# SBC_65C02_IRQ_BigBoard_v9-1-3.net
KiCad netlist of a schematic drawn in EAGLE
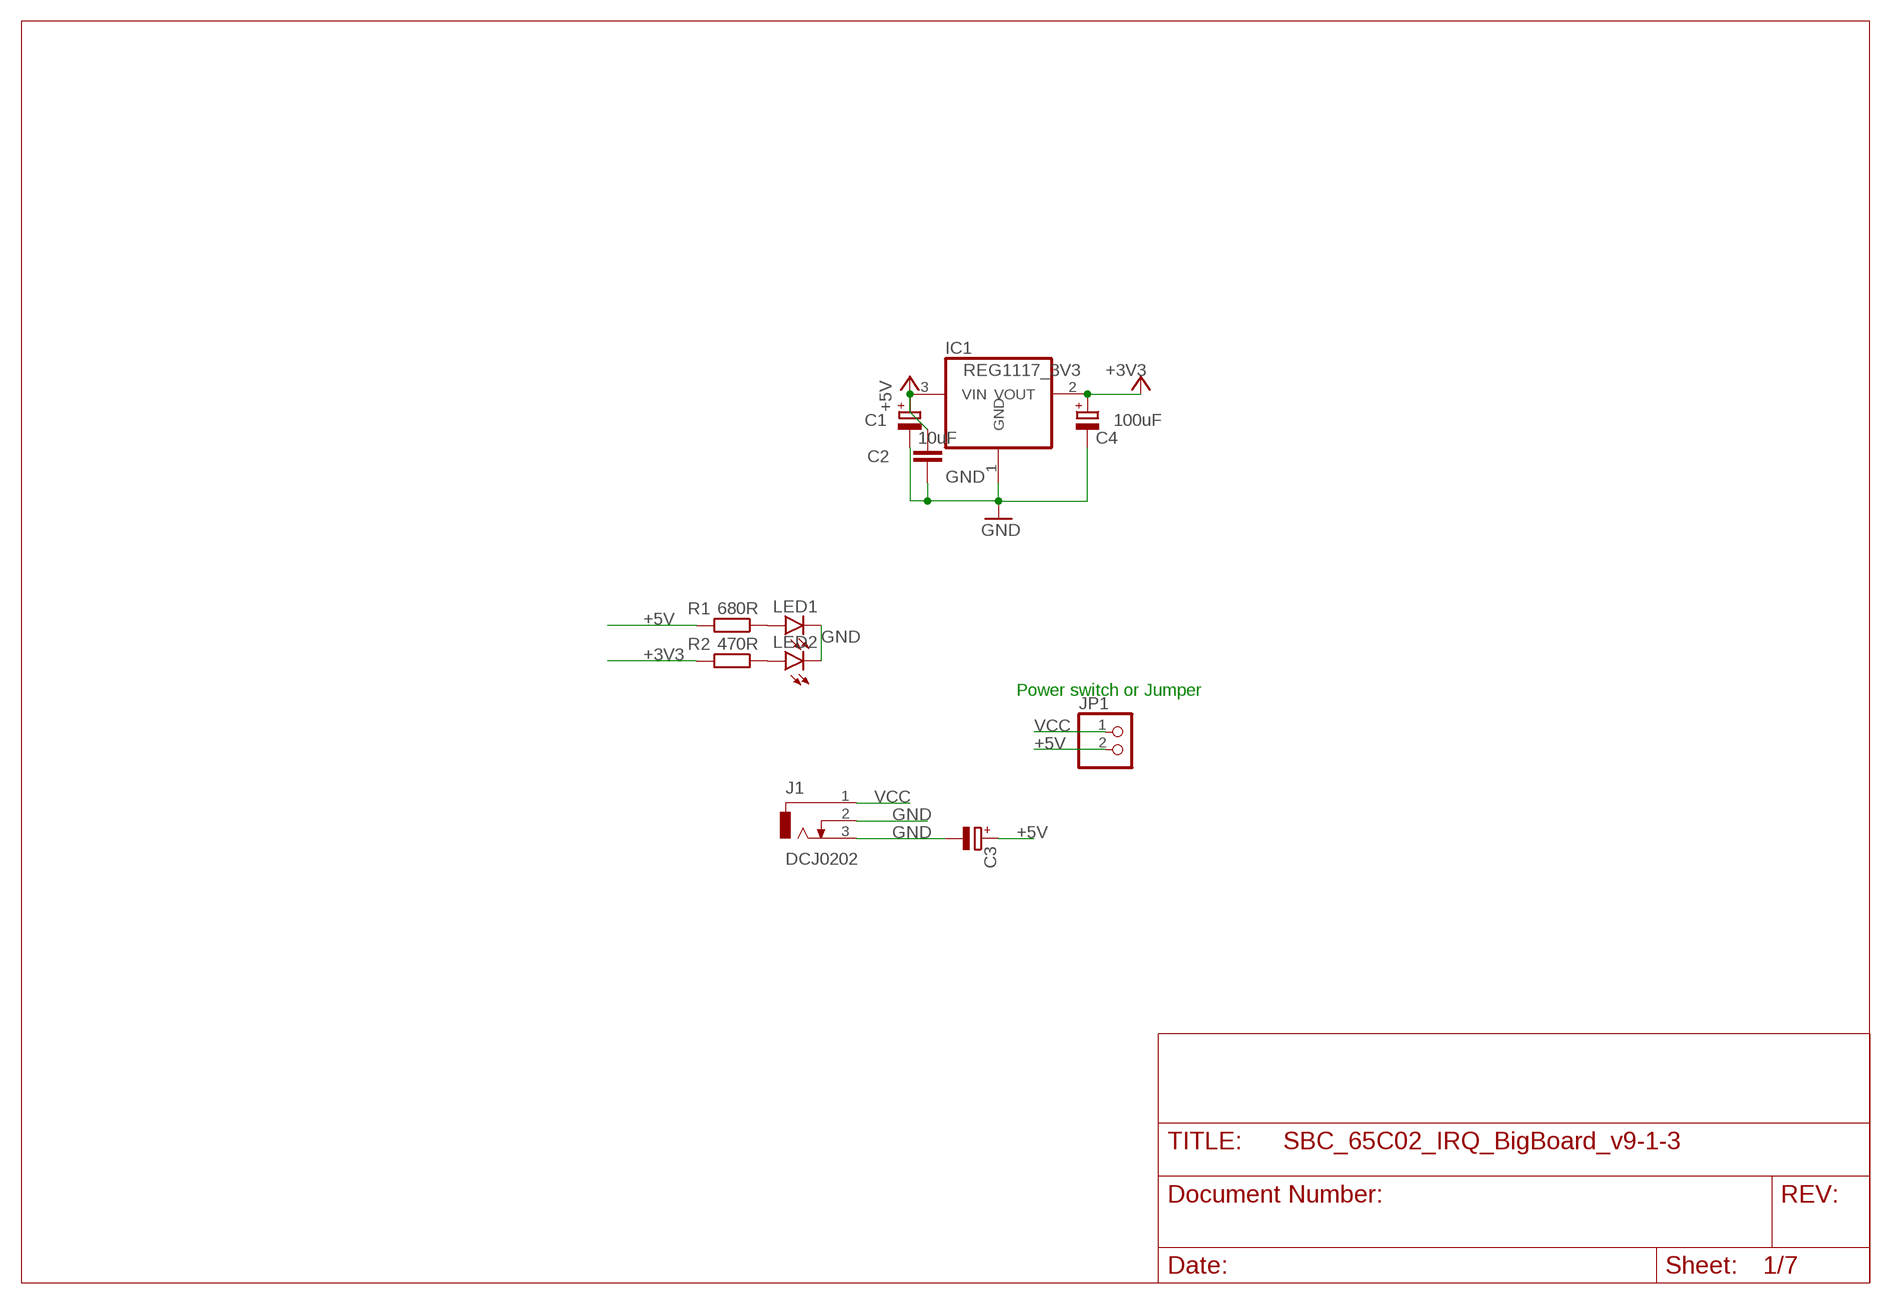
[diagram p0: schematic, sheet 1]
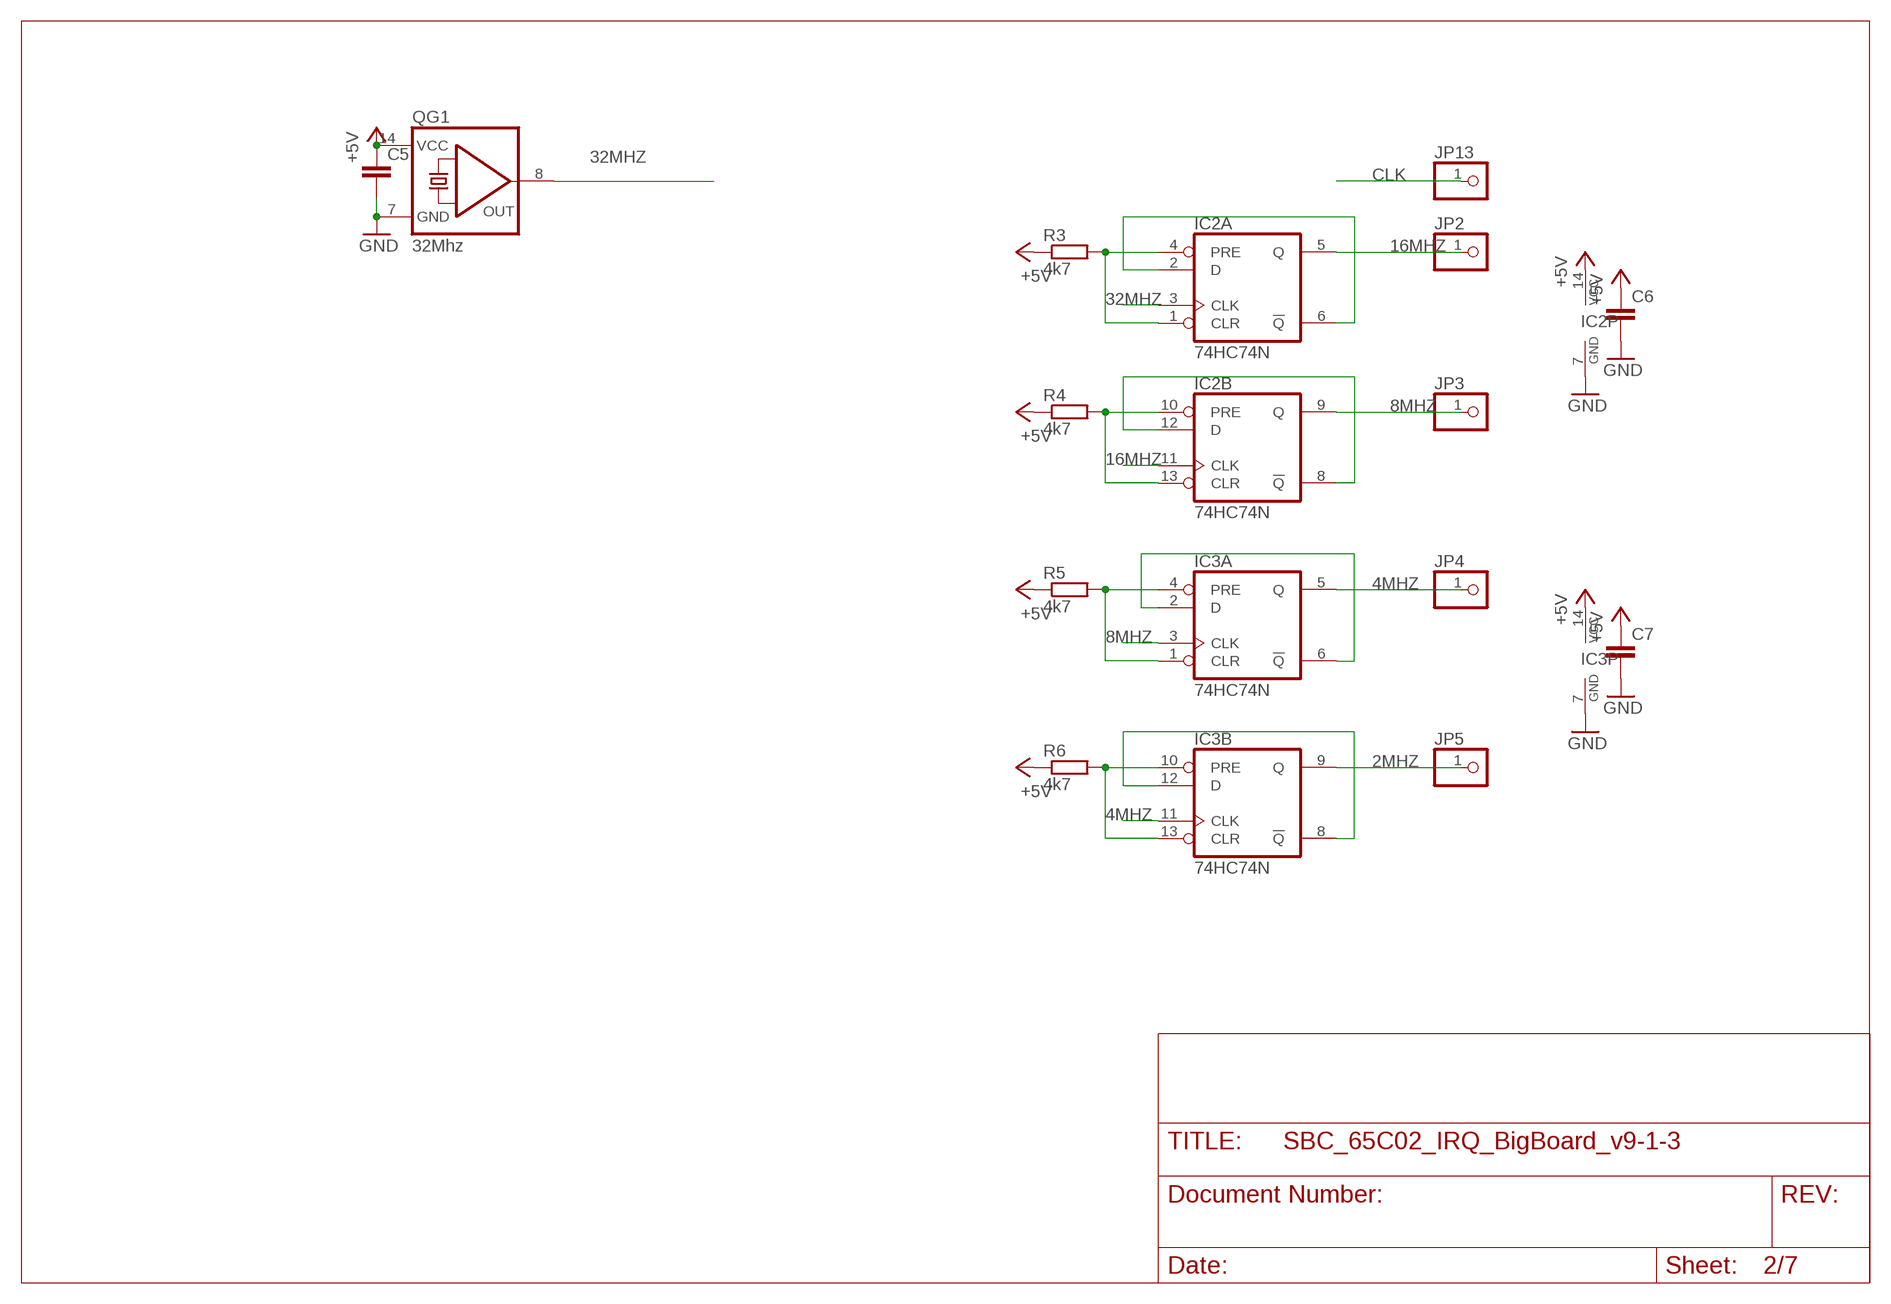
[diagram p1: schematic, sheet 2]
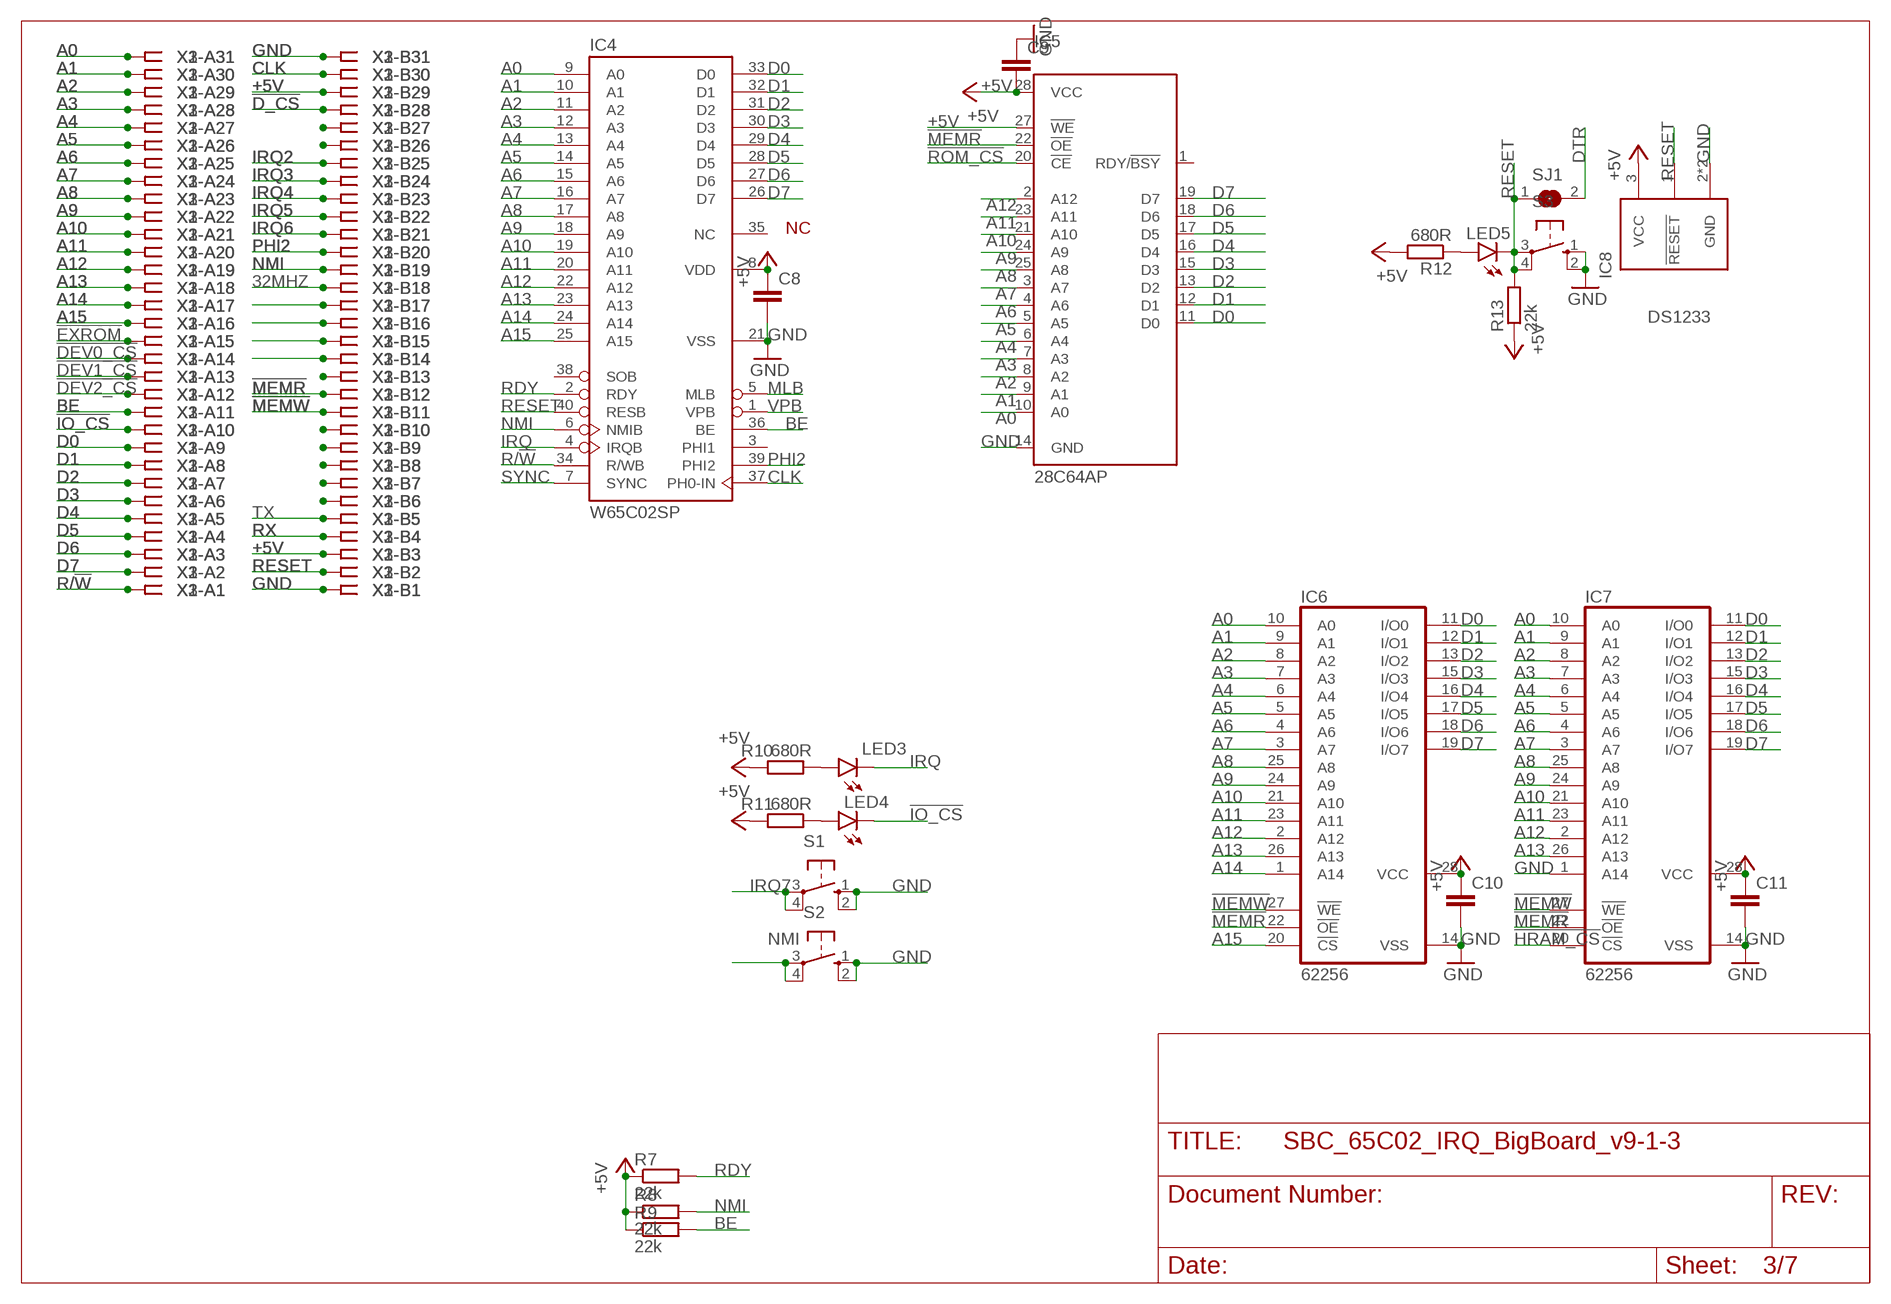
[diagram p2: schematic, sheet 3]
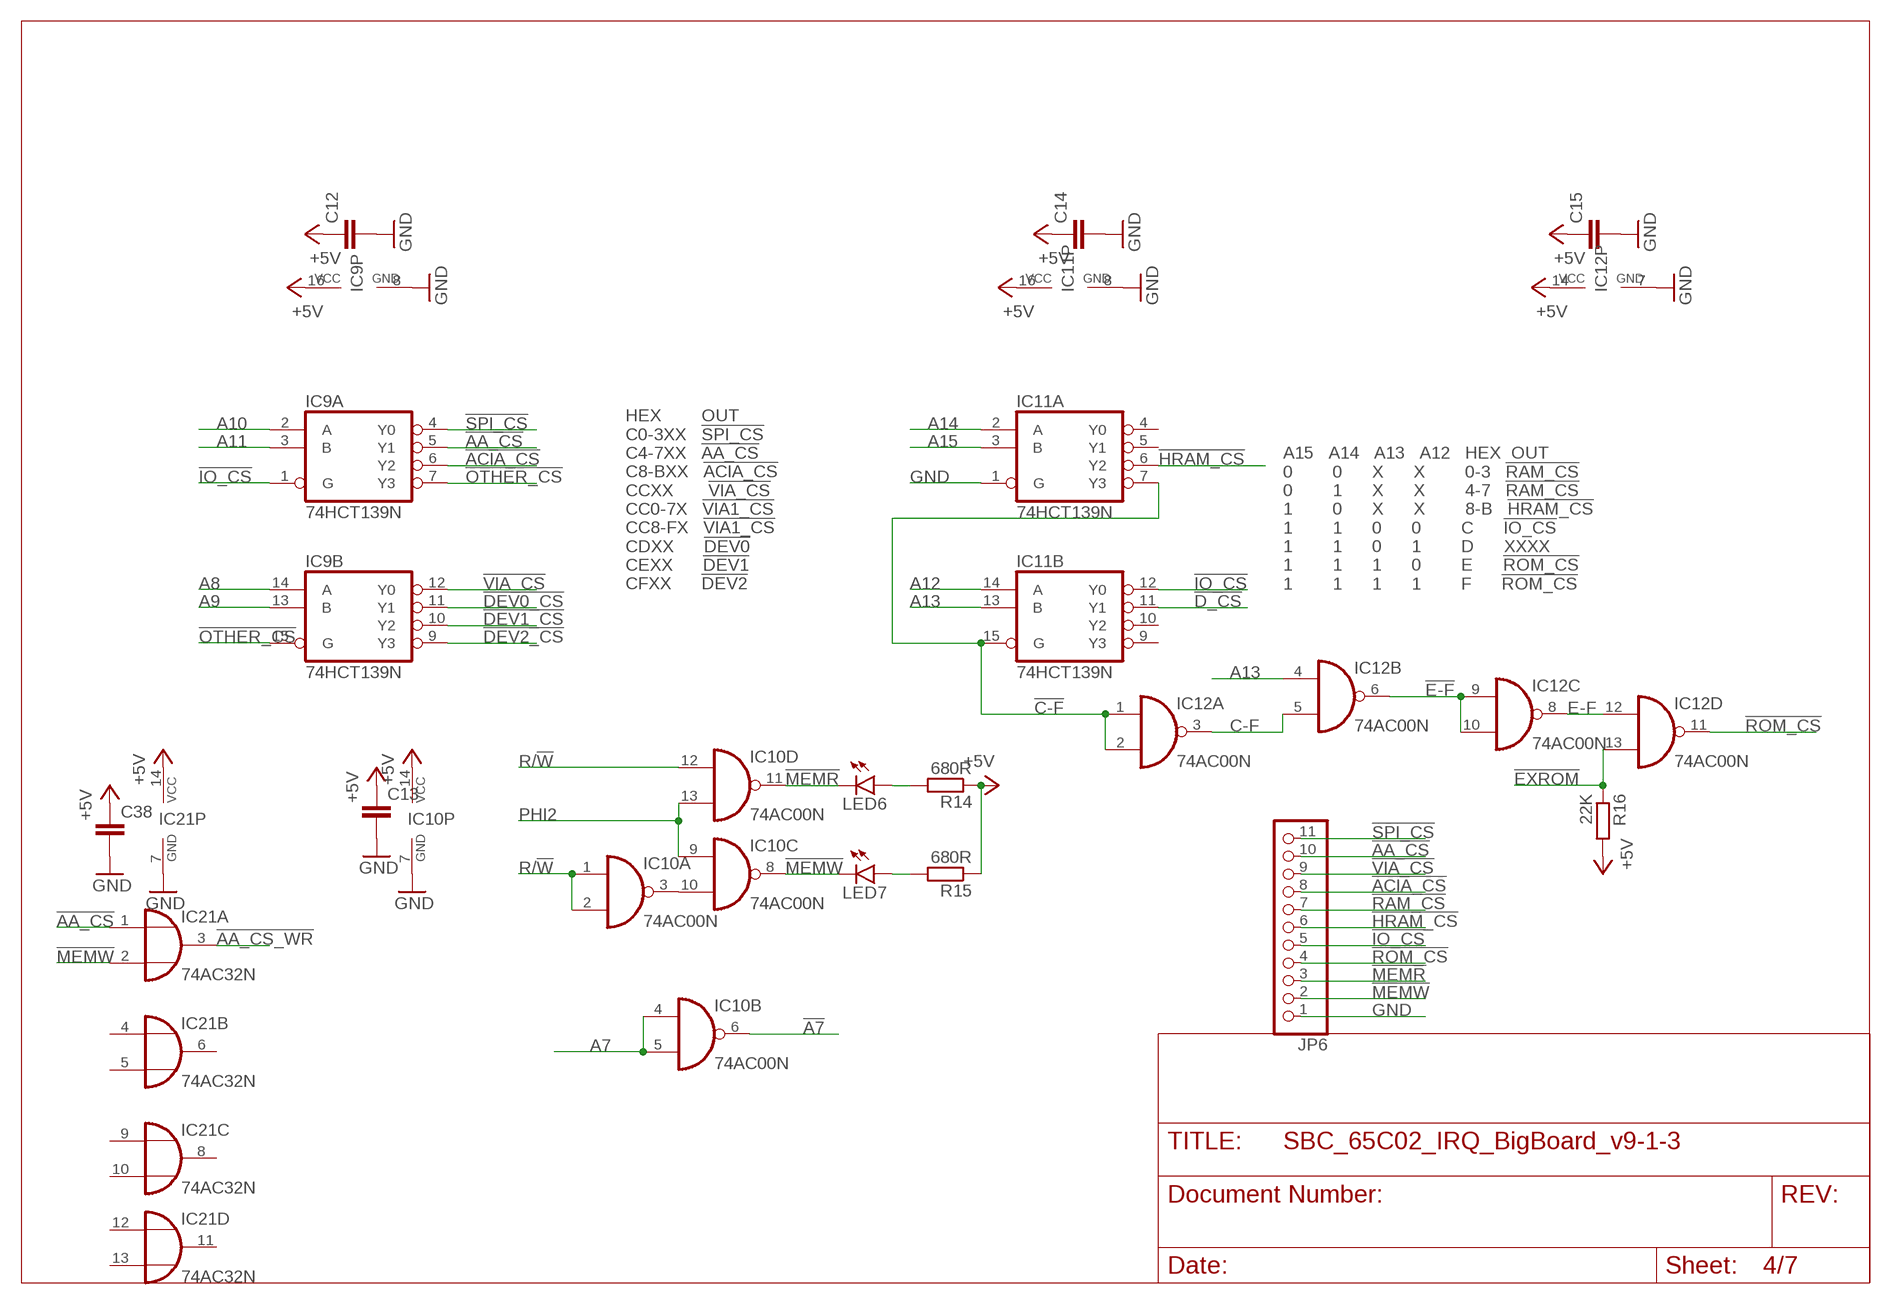
[diagram p3: schematic, sheet 4]
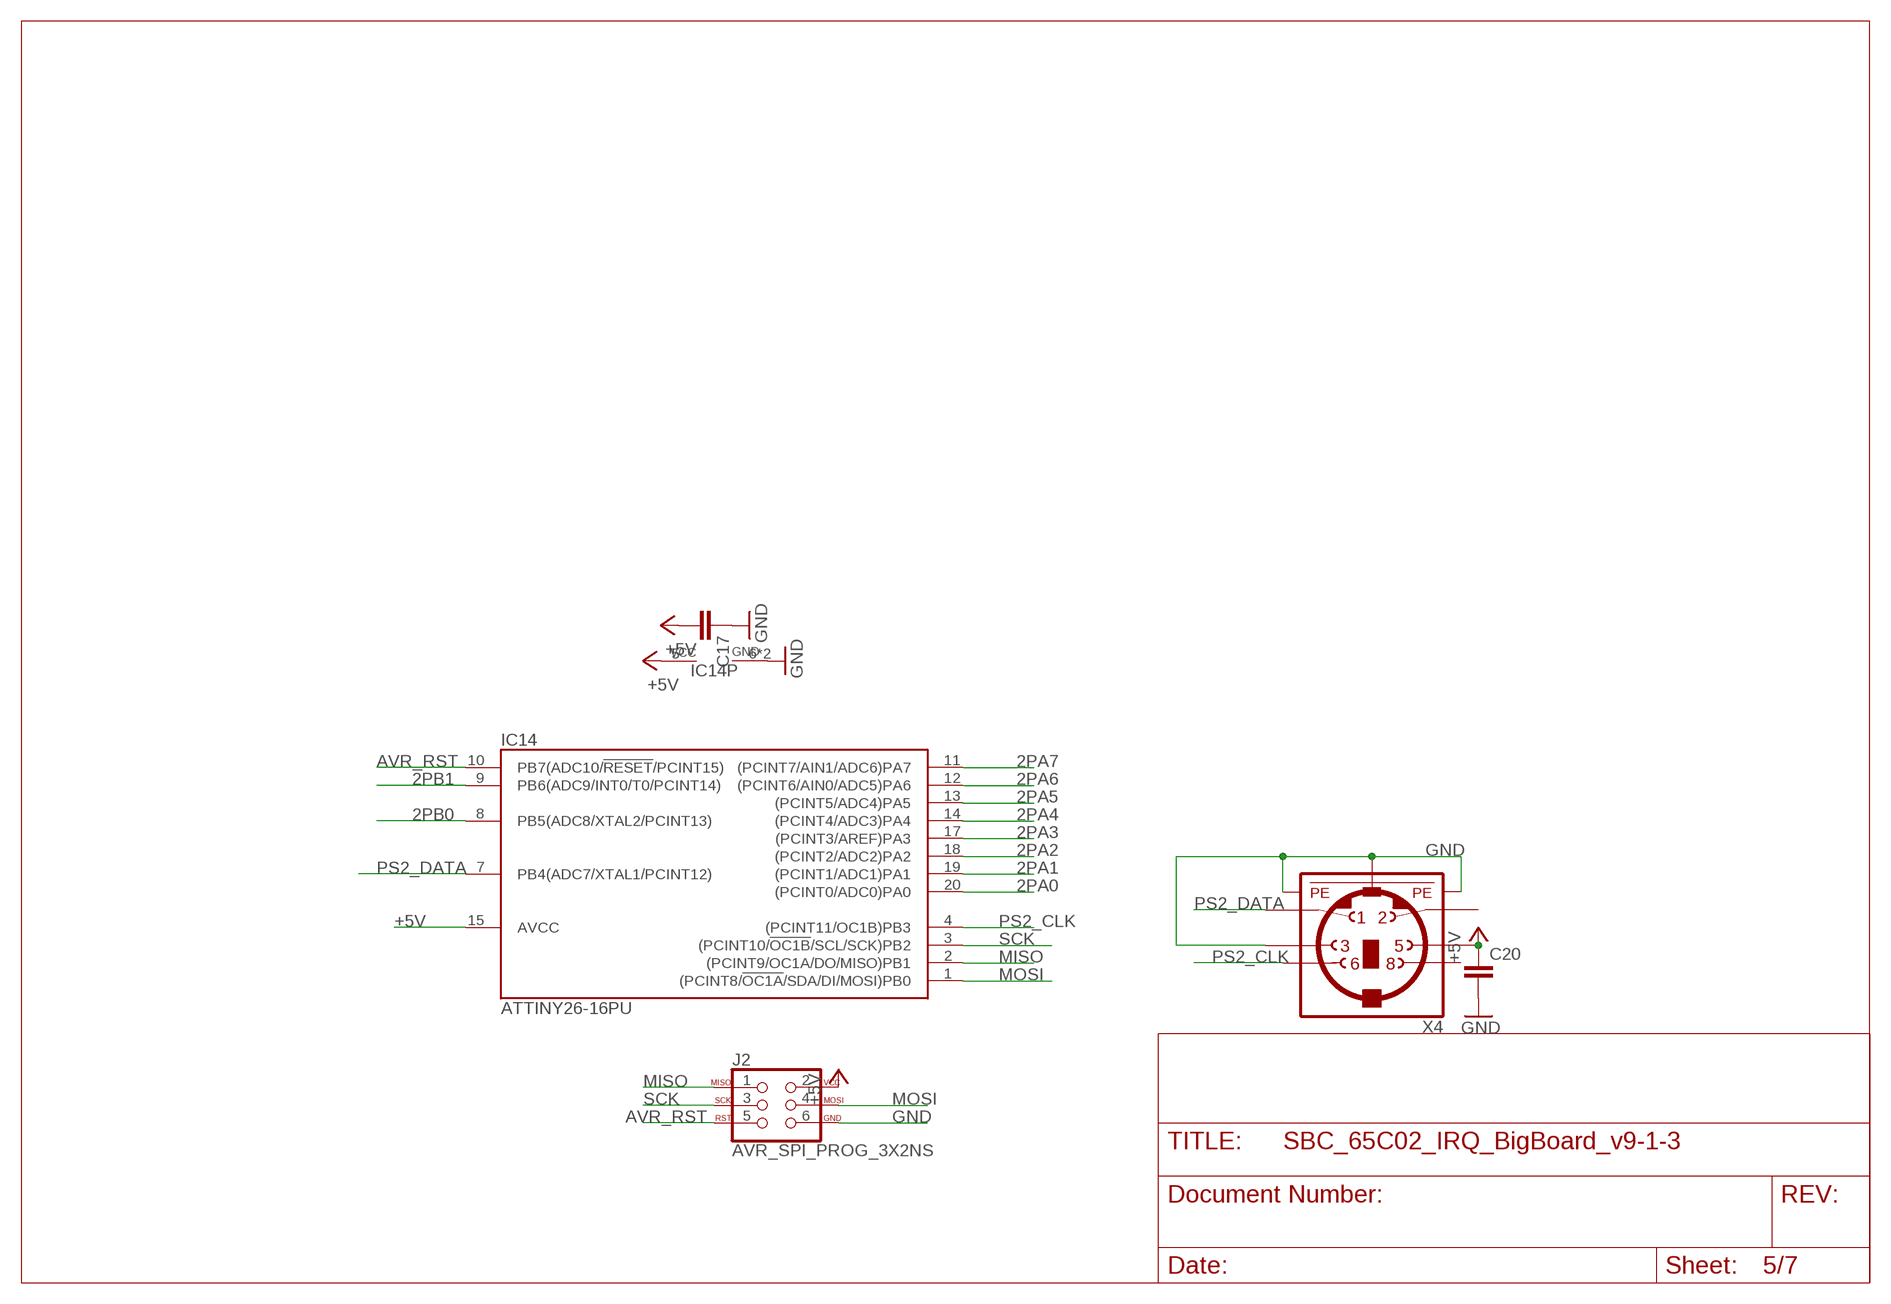
[diagram p4: schematic, sheet 5]
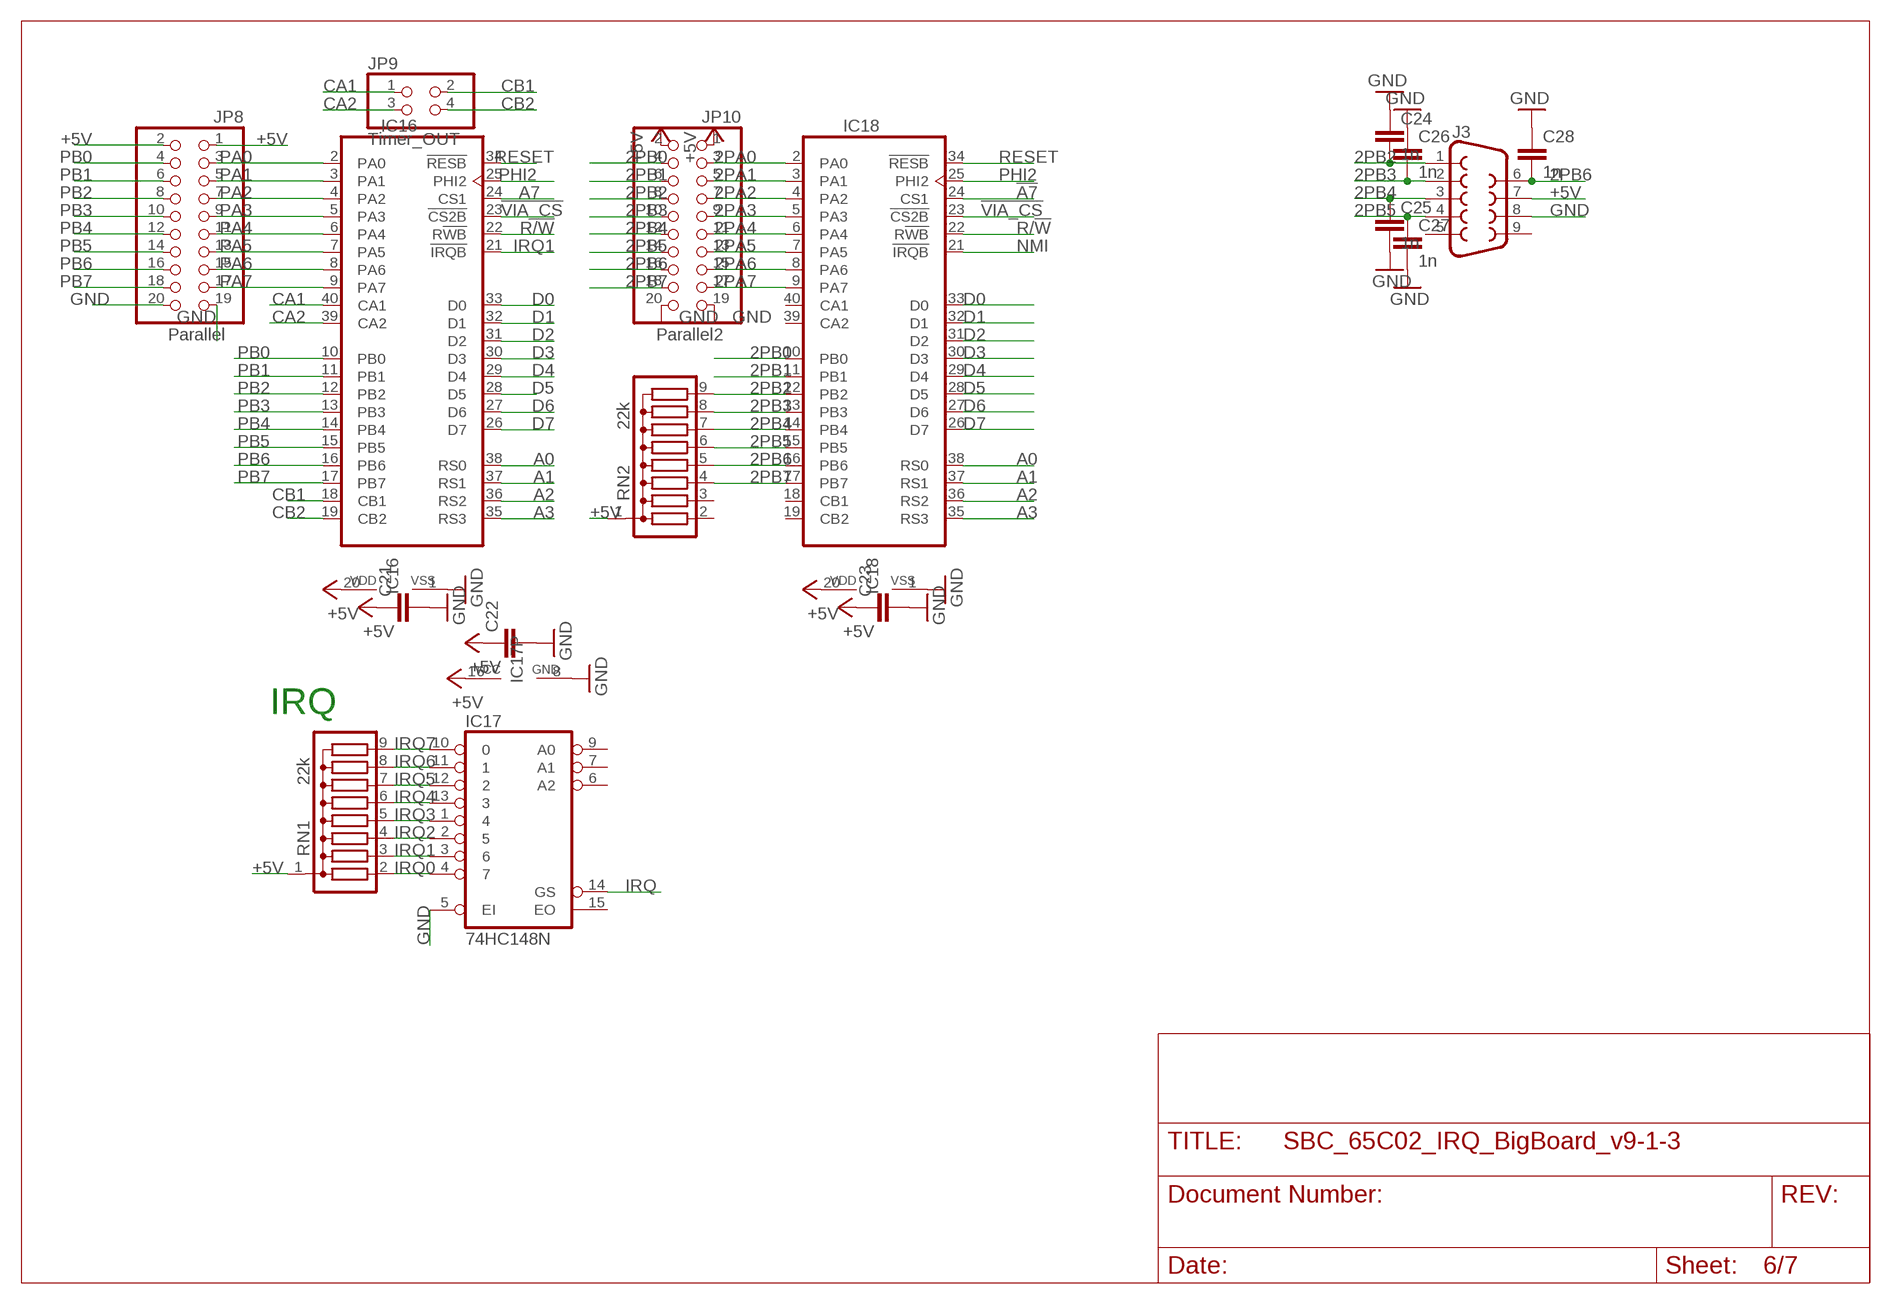
[diagram p5: schematic, sheet 6]
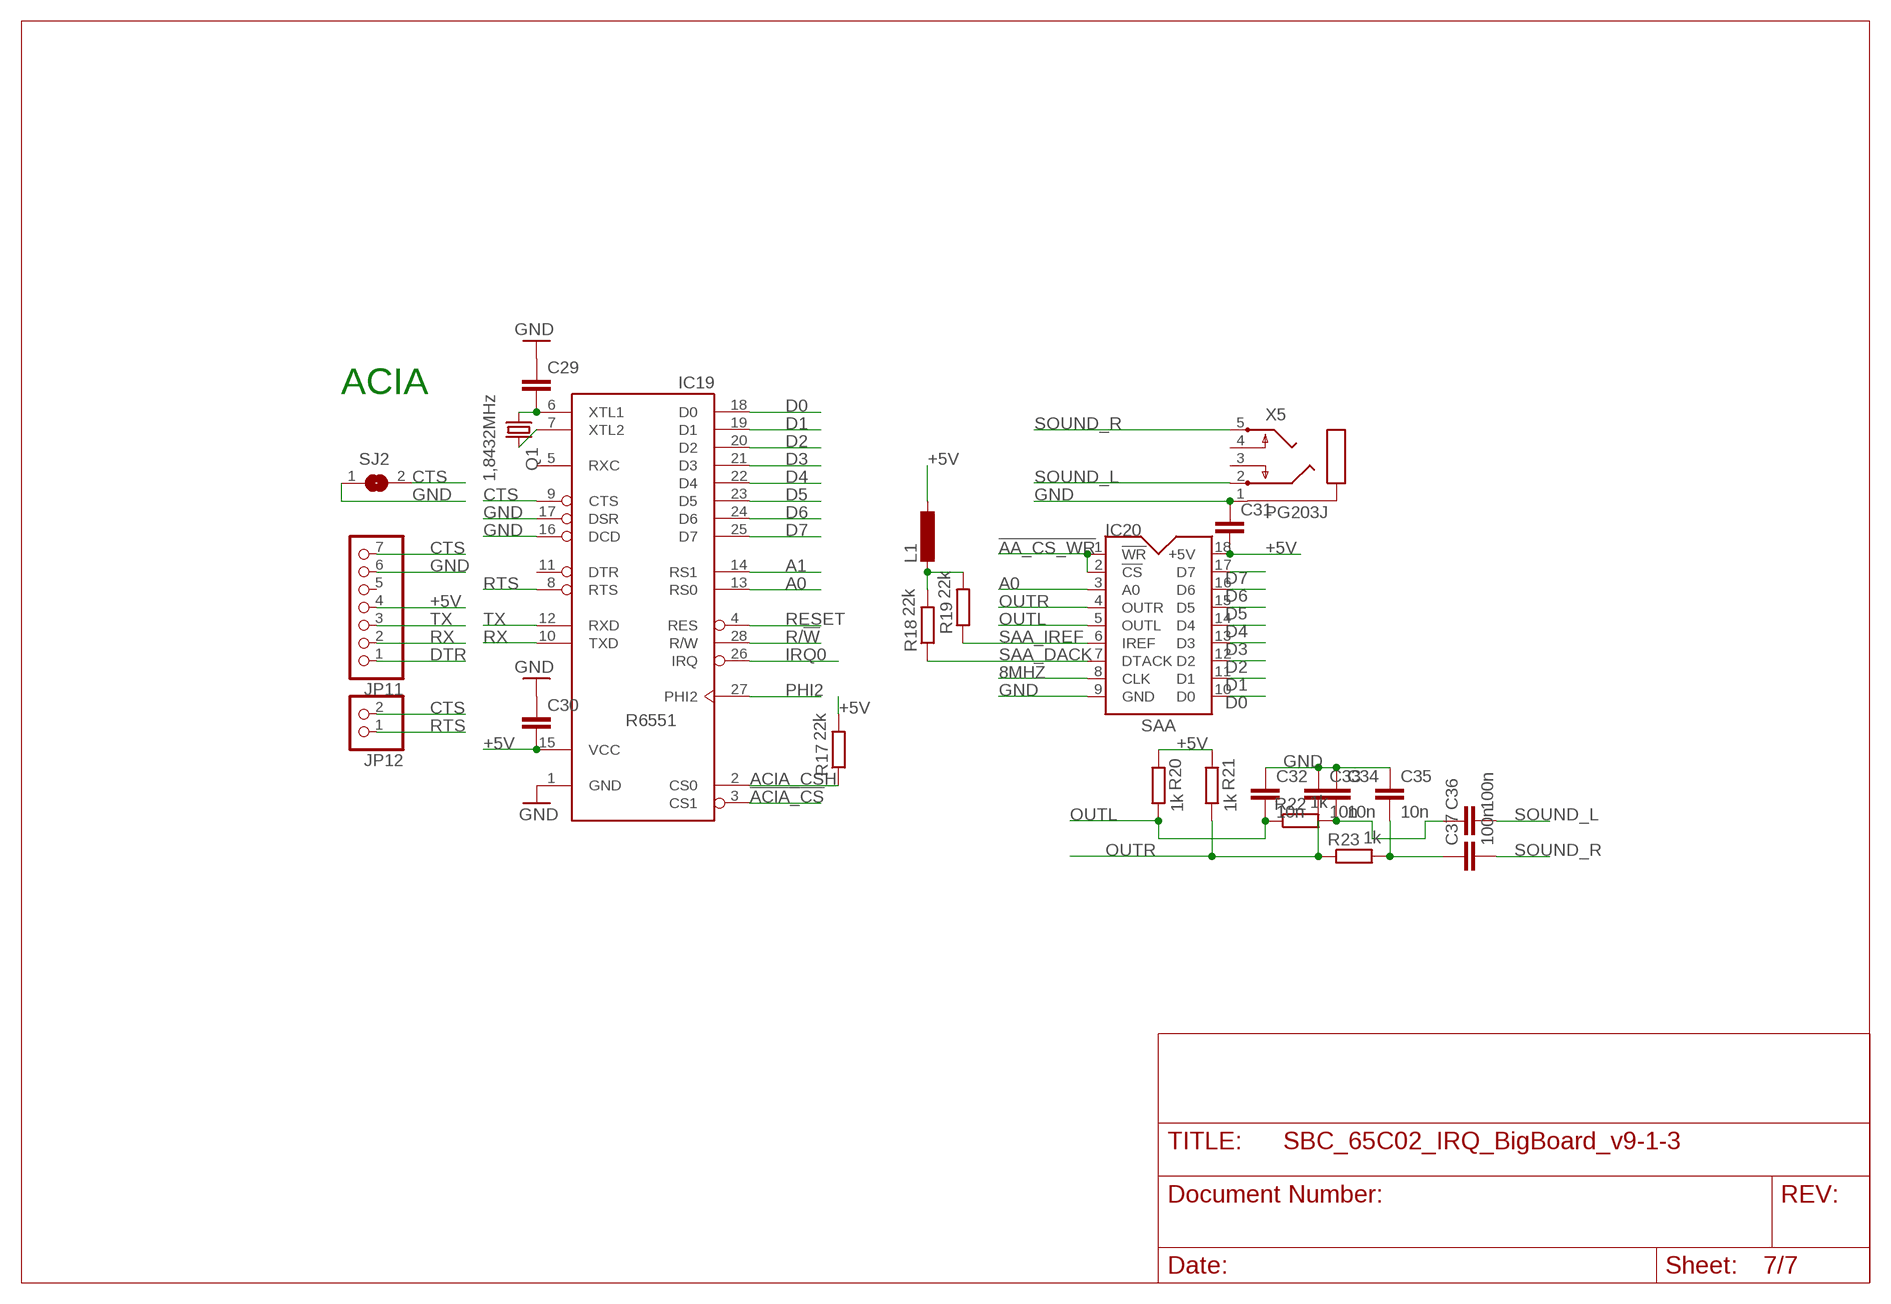
[diagram p6: schematic, sheet 7]

(export (version "E")
  (design (tool "Eeschema 10.0.6"))
  (components
    (comp (ref "C17")
      (value "C-EU050-025X075")
      (footprint "eagle-import:C050-025X075")
      (libsource (lib "eagle-import") (part "C-EU050-025X075"))
    )
    (comp (ref "C20")
      (value "C-EU050-025X075")
      (footprint "eagle-import:C050-025X075")
      (libsource (lib "eagle-import") (part "C-EU050-025X075"))
    )
    (comp (ref "IC14")
      (value "ATTINY26-16PU")
      (footprint "eagle-import:DIL20")
      (libsource (lib "eagle-import") (part "ATTINY26PU-16"))
    )
    (comp (ref "J2")
      (value "AVR_SPI_PROG_3X2NS")
      (footprint "eagle-import:2X3-NS")
      (libsource (lib "eagle-import") (part "AVR_SPI_PROG_3X2NS"))
    )
    (comp (ref "X4")
      (value "MINI_DIN_6")
      (footprint "eagle-import:M_DIN6")
      (libsource (lib "eagle-import") (part "MINI_DIN_6"))
    )
    (comp (ref "C1")
      (value "10uF")
      (footprint "eagle-import:E2,5-5")
      (libsource (lib "eagle-import") (part "CPOL-EUE2.5-5"))
    )
    (comp (ref "C2")
      (value "C-EU050-035X075")
      (footprint "eagle-import:C050-035X075")
      (libsource (lib "eagle-import") (part "C-EU050-035X075"))
    )
    (comp (ref "C3")
      (value "CPOL-EUE2.5-5")
      (footprint "eagle-import:E2,5-5")
      (libsource (lib "eagle-import") (part "CPOL-EUE2.5-5"))
    )
    (comp (ref "C4")
      (value "100uF")
      (footprint "eagle-import:E2,5-5")
      (libsource (lib "eagle-import") (part "CPOL-EUE2.5-5"))
    )
    (comp (ref "IC1")
      (value "REG1117_3V3")
      (footprint "eagle-import:SOT223")
      (fields (field (name "MPN") "REG1117"))
      (libsource (lib "eagle-import") (part "REG1117"))
    )
    (comp (ref "J1")
      (value "DCJ0202")
      (footprint "eagle-import:DCJ0202")
      (libsource (lib "eagle-import") (part "DCJ0202"))
    )
    (comp (ref "JP1")
      (value "PINHD-1X2")
      (footprint "eagle-import:1X02")
      (libsource (lib "eagle-import") (part "PINHD-1X2"))
    )
    (comp (ref "LED1")
      (value "LED5MM")
      (footprint "eagle-import:LED5MM")
      (libsource (lib "eagle-import") (part "LED5MM"))
    )
    (comp (ref "LED2")
      (value "LED5MM")
      (footprint "eagle-import:LED5MM")
      (libsource (lib "eagle-import") (part "LED5MM"))
    )
    (comp (ref "R1")
      (value "680R")
      (footprint "eagle-import:0207_10")
      (libsource (lib "eagle-import") (part "resistor_348_R-EU_0207/10"))
    )
    (comp (ref "R2")
      (value "470R")
      (footprint "eagle-import:0207_10")
      (libsource (lib "eagle-import") (part "resistor_348_R-EU_0207/10"))
    )
    (comp (ref "C29")
      (value "C-EU050-025X075")
      (footprint "eagle-import:C050-025X075")
      (libsource (lib "eagle-import") (part "C-EU050-025X075"))
    )
    (comp (ref "C30")
      (value "C-EU050-025X075")
      (footprint "eagle-import:C050-025X075")
      (libsource (lib "eagle-import") (part "C-EU050-025X075"))
    )
    (comp (ref "C31")
      (value "C-EU050-025X075")
      (footprint "eagle-import:C050-025X075")
      (libsource (lib "eagle-import") (part "C-EU050-025X075"))
    )
    (comp (ref "C32")
      (value "10n")
      (footprint "eagle-import:C050-025X075")
      (libsource (lib "eagle-import") (part "C-EU050-025X075"))
    )
    (comp (ref "C33")
      (value "10n")
      (footprint "eagle-import:C050-025X075")
      (libsource (lib "eagle-import") (part "C-EU050-025X075"))
    )
    (comp (ref "C34")
      (value "10n")
      (footprint "eagle-import:C050-025X075")
      (libsource (lib "eagle-import") (part "C-EU050-025X075"))
    )
    (comp (ref "C35")
      (value "10n")
      (footprint "eagle-import:C050-025X075")
      (libsource (lib "eagle-import") (part "C-EU050-025X075"))
    )
    (comp (ref "C36")
      (value "100n")
      (footprint "eagle-import:C050-025X075")
      (libsource (lib "eagle-import") (part "C-EU050-025X075"))
    )
    (comp (ref "C37")
      (value "100n")
      (footprint "eagle-import:C050-025X075")
      (libsource (lib "eagle-import") (part "C-EU050-025X075"))
    )
    (comp (ref "IC19")
      (value "R6551")
      (footprint "eagle-import:DIP-28")
      (libsource (lib "eagle-import") (part "R6551"))
    )
    (comp (ref "IC20")
      (value "SAA")
      (footprint "eagle-import:DIL18")
      (libsource (lib "eagle-import") (part "SAA1099DIL18"))
    )
    (comp (ref "JP11")
      (value "PINHD-1X7")
      (footprint "eagle-import:1X07")
      (libsource (lib "eagle-import") (part "PINHD-1X7"))
    )
    (comp (ref "JP12")
      (value "PINHD-1X2")
      (footprint "eagle-import:1X02")
      (libsource (lib "eagle-import") (part "PINHD-1X2"))
    )
    (comp (ref "L1")
      (value "L-EU0207/10")
      (footprint "eagle-import:0207_10")
      (libsource (lib "eagle-import") (part "L-EU0207/10"))
    )
    (comp (ref "Q1")
      (value "1,8432MHz")
      (footprint "eagle-import:HC49_S")
      (libsource (lib "eagle-import") (part "CRYSTALHC49S"))
    )
    (comp (ref "R17")
      (value "22k")
      (footprint "eagle-import:0207_10")
      (libsource (lib "eagle-import") (part "rcl_334_R-EU_0207/10"))
    )
    (comp (ref "R18")
      (value "22k")
      (footprint "eagle-import:0207_10")
      (libsource (lib "eagle-import") (part "rcl_334_R-EU_0207/10"))
    )
    (comp (ref "R19")
      (value "22k")
      (footprint "eagle-import:0207_10")
      (libsource (lib "eagle-import") (part "rcl_334_R-EU_0207/10"))
    )
    (comp (ref "R20")
      (value "1k")
      (footprint "eagle-import:0207_10")
      (libsource (lib "eagle-import") (part "rcl_334_R-EU_0207/10"))
    )
    (comp (ref "R21")
      (value "1k")
      (footprint "eagle-import:0207_10")
      (libsource (lib "eagle-import") (part "rcl_334_R-EU_0207/10"))
    )
    (comp (ref "R22")
      (value "1k")
      (footprint "eagle-import:0207_10")
      (libsource (lib "eagle-import") (part "rcl_334_R-EU_0207/10"))
    )
    (comp (ref "R23")
      (value "1k")
      (footprint "eagle-import:0207_10")
      (libsource (lib "eagle-import") (part "rcl_334_R-EU_0207/10"))
    )
    (comp (ref "SJ2") (value "SJ") (footprint "eagle-import:SJ") (libsource (lib "eagle-import") (part "SJ")))
    (comp (ref "X5")
      (value "PG203J")
      (footprint "eagle-import:PG203J")
      (libsource (lib "eagle-import") (part "PG203J"))
    )
    (comp (ref "C21")
      (value "C-EU050-025X075")
      (footprint "eagle-import:C050-025X075")
      (libsource (lib "eagle-import") (part "C-EU050-025X075"))
    )
    (comp (ref "C22")
      (value "C-EU050-025X075")
      (footprint "eagle-import:C050-025X075")
      (libsource (lib "eagle-import") (part "C-EU050-025X075"))
    )
    (comp (ref "C23")
      (value "C-EU050-025X075")
      (footprint "eagle-import:C050-025X075")
      (libsource (lib "eagle-import") (part "C-EU050-025X075"))
    )
    (comp (ref "C24")
      (value "1n")
      (footprint "eagle-import:C050-025X075")
      (libsource (lib "eagle-import") (part "C-EU050-025X075"))
    )
    (comp (ref "C25")
      (value "1n")
      (footprint "eagle-import:C050-025X075")
      (libsource (lib "eagle-import") (part "C-EU050-025X075"))
    )
    (comp (ref "C26")
      (value "1n")
      (footprint "eagle-import:C050-025X075")
      (libsource (lib "eagle-import") (part "C-EU050-025X075"))
    )
    (comp (ref "C27")
      (value "1n")
      (footprint "eagle-import:C050-025X075")
      (libsource (lib "eagle-import") (part "C-EU050-025X075"))
    )
    (comp (ref "C28")
      (value "1n")
      (footprint "eagle-import:C050-025X075")
      (libsource (lib "eagle-import") (part "C-EU050-025X075"))
    )
    (comp (ref "IC16")
      (value "W65C22S6TP")
      (footprint "eagle-import:DIL40")
      (libsource (lib "eagle-import") (part "W65C22SP6T"))
    )
    (comp (ref "IC17")
      (value "74HC148N")
      (footprint "eagle-import:DIL16")
      (libsource (lib "eagle-import") (part "74148NHC"))
    )
    (comp (ref "IC18")
      (value "W65C22S6TP")
      (footprint "eagle-import:DIL40")
      (libsource (lib "eagle-import") (part "W65C22SP6T"))
    )
    (comp (ref "J3")
      (value "DB9MALE")
      (footprint "eagle-import:DB9_MALE")
      (libsource (lib "eagle-import") (part "DB9MALE"))
    )
    (comp (ref "JP8")
      (value "Parallel")
      (footprint "eagle-import:2X10")
      (libsource (lib "eagle-import") (part "PINHD-2X10"))
    )
    (comp (ref "JP9")
      (value "Timer_OUT")
      (footprint "eagle-import:2X02")
      (libsource (lib "eagle-import") (part "PINHD-2X2"))
    )
    (comp (ref "JP10")
      (value "Parallel2")
      (footprint "eagle-import:2X10")
      (libsource (lib "eagle-import") (part "PINHD-2X10"))
    )
    (comp (ref "RN1")
      (value "22k")
      (footprint "eagle-import:SIL9")
      (libsource (lib "eagle-import") (part "G08R"))
    )
    (comp (ref "RN2")
      (value "22k")
      (footprint "eagle-import:SIL9")
      (libsource (lib "eagle-import") (part "G08R"))
    )
    (comp (ref "C5")
      (value "C-EU050-025X075")
      (footprint "eagle-import:C050-025X075")
      (libsource (lib "eagle-import") (part "C-EU050-025X075"))
    )
    (comp (ref "C6")
      (value "C-EU050-025X075")
      (footprint "eagle-import:C050-025X075")
      (libsource (lib "eagle-import") (part "C-EU050-025X075"))
    )
    (comp (ref "C7")
      (value "C-EU050-025X075")
      (footprint "eagle-import:C050-025X075")
      (libsource (lib "eagle-import") (part "C-EU050-025X075"))
    )
    (comp (ref "IC2")
      (value "74HC74N")
      (footprint "eagle-import:DIL14")
      (libsource (lib "eagle-import") (part "7474NHC"))
    )
    (comp (ref "IC3")
      (value "74HC74N")
      (footprint "eagle-import:DIL14")
      (libsource (lib "eagle-import") (part "7474NHC"))
    )
    (comp (ref "JP2")
      (value "PINHD-1X1")
      (footprint "eagle-import:1X01")
      (libsource (lib "eagle-import") (part "PINHD-1X1"))
    )
    (comp (ref "JP3")
      (value "PINHD-1X1")
      (footprint "eagle-import:1X01")
      (libsource (lib "eagle-import") (part "PINHD-1X1"))
    )
    (comp (ref "JP4")
      (value "PINHD-1X1")
      (footprint "eagle-import:1X01")
      (libsource (lib "eagle-import") (part "PINHD-1X1"))
    )
    (comp (ref "JP5")
      (value "PINHD-1X1")
      (footprint "eagle-import:1X01")
      (libsource (lib "eagle-import") (part "PINHD-1X1"))
    )
    (comp (ref "JP13")
      (value "PINHD-1X1")
      (footprint "eagle-import:1X01")
      (libsource (lib "eagle-import") (part "PINHD-1X1"))
    )
    (comp (ref "QG1")
      (value "32Mhz")
      (footprint "eagle-import:DIL14S")
      (libsource (lib "eagle-import") (part "QG5860"))
    )
    (comp (ref "R3")
      (value "4k7")
      (footprint "eagle-import:0204_7")
      (libsource (lib "eagle-import") (part "rcl_334_R-EU_0204/7"))
    )
    (comp (ref "R4")
      (value "4k7")
      (footprint "eagle-import:0204_7")
      (libsource (lib "eagle-import") (part "rcl_334_R-EU_0204/7"))
    )
    (comp (ref "R5")
      (value "4k7")
      (footprint "eagle-import:0204_7")
      (libsource (lib "eagle-import") (part "rcl_334_R-EU_0204/7"))
    )
    (comp (ref "R6")
      (value "4k7")
      (footprint "eagle-import:0204_7")
      (libsource (lib "eagle-import") (part "rcl_334_R-EU_0204/7"))
    )
    (comp (ref "C12")
      (value "C-EU050-025X075")
      (footprint "eagle-import:C050-025X075")
      (libsource (lib "eagle-import") (part "C-EU050-025X075"))
    )
    (comp (ref "C13")
      (value "C-EU050-025X075")
      (footprint "eagle-import:C050-025X075")
      (libsource (lib "eagle-import") (part "C-EU050-025X075"))
    )
    (comp (ref "C14")
      (value "C-EU050-025X075")
      (footprint "eagle-import:C050-025X075")
      (libsource (lib "eagle-import") (part "C-EU050-025X075"))
    )
    (comp (ref "C15")
      (value "C-EU050-025X075")
      (footprint "eagle-import:C050-025X075")
      (libsource (lib "eagle-import") (part "C-EU050-025X075"))
    )
    (comp (ref "C38")
      (value "C-EU050-025X075")
      (footprint "eagle-import:C050-025X075")
      (libsource (lib "eagle-import") (part "C-EU050-025X075"))
    )
    (comp (ref "IC9")
      (value "74HCT139N")
      (footprint "eagle-import:DIL16")
      (libsource (lib "eagle-import") (part "74139NHCT"))
    )
    (comp (ref "IC10")
      (value "74AC00N")
      (footprint "eagle-import:DIL14")
      (libsource (lib "eagle-import") (part "7400NAC"))
    )
    (comp (ref "IC11")
      (value "74HCT139N")
      (footprint "eagle-import:DIL16")
      (libsource (lib "eagle-import") (part "74139NHCT"))
    )
    (comp (ref "IC12")
      (value "74AC00N")
      (footprint "eagle-import:DIL14")
      (libsource (lib "eagle-import") (part "7400NAC"))
    )
    (comp (ref "IC21")
      (value "74AC32N")
      (footprint "eagle-import:DIL14")
      (libsource (lib "eagle-import") (part "7432NAC"))
    )
    (comp (ref "JP6")
      (value "PINHD-1X11")
      (footprint "eagle-import:1X11")
      (libsource (lib "eagle-import") (part "PINHD-1X11"))
    )
    (comp (ref "LED6")
      (value "LED5MM")
      (footprint "eagle-import:LED5MM")
      (libsource (lib "eagle-import") (part "LED5MM"))
    )
    (comp (ref "LED7")
      (value "LED5MM")
      (footprint "eagle-import:LED5MM")
      (libsource (lib "eagle-import") (part "LED5MM"))
    )
    (comp (ref "R14")
      (value "680R")
      (footprint "eagle-import:0207_10")
      (libsource (lib "eagle-import") (part "rcl_334_R-EU_0207/10"))
    )
    (comp (ref "R15")
      (value "680R")
      (footprint "eagle-import:0207_10")
      (libsource (lib "eagle-import") (part "rcl_334_R-EU_0207/10"))
    )
    (comp (ref "R16")
      (value "22K")
      (footprint "eagle-import:0207_10")
      (libsource (lib "eagle-import") (part "rcl_334_R-EU_0207/10"))
    )
    (comp (ref "C8")
      (value "C-EU050-025X075")
      (footprint "eagle-import:C050-025X075")
      (libsource (lib "eagle-import") (part "C-EU050-025X075"))
    )
    (comp (ref "C9")
      (value "C-EU050-025X075")
      (footprint "eagle-import:C050-025X075")
      (libsource (lib "eagle-import") (part "C-EU050-025X075"))
    )
    (comp (ref "C10")
      (value "C-EU050-025X075")
      (footprint "eagle-import:C050-025X075")
      (libsource (lib "eagle-import") (part "C-EU050-025X075"))
    )
    (comp (ref "C11")
      (value "C-EU050-025X075")
      (footprint "eagle-import:C050-025X075")
      (libsource (lib "eagle-import") (part "C-EU050-025X075"))
    )
    (comp (ref "IC4")
      (value "W65C02SP")
      (footprint "eagle-import:DIL40")
      (libsource (lib "eagle-import") (part "W65C02SP"))
    )
    (comp (ref "IC5")
      (value "28C64AP")
      (footprint "eagle-import:DIL28-6")
      (fields (field (name "MPN") "AT28C64B-15PU"))
      (libsource (lib "eagle-import") (part "2864APC"))
    )
    (comp (ref "IC6")
      (value "62256")
      (footprint "eagle-import:DIL28-6")
      (libsource (lib "eagle-import") (part "62256P"))
    )
    (comp (ref "IC7")
      (value "62256")
      (footprint "eagle-import:DIL28-6")
      (libsource (lib "eagle-import") (part "62256P"))
    )
    (comp (ref "IC8")
      (value "DS1233")
      (footprint "eagle-import:SOT223")
      (libsource (lib "eagle-import") (part "DS1233SOT223"))
    )
    (comp (ref "LED3")
      (value "LED5MM")
      (footprint "eagle-import:LED5MM")
      (libsource (lib "eagle-import") (part "LED5MM"))
    )
    (comp (ref "LED4")
      (value "LED5MM")
      (footprint "eagle-import:LED5MM")
      (libsource (lib "eagle-import") (part "LED5MM"))
    )
    (comp (ref "LED5")
      (value "LED5MM")
      (footprint "eagle-import:LED5MM")
      (libsource (lib "eagle-import") (part "LED5MM"))
    )
    (comp (ref "R7")
      (value "22k")
      (footprint "eagle-import:0207_10")
      (libsource (lib "eagle-import") (part "R-EU_0207/10"))
    )
    (comp (ref "R8")
      (value "22k")
      (footprint "eagle-import:0207_10")
      (libsource (lib "eagle-import") (part "R-EU_0207/10"))
    )
    (comp (ref "R9")
      (value "22k")
      (footprint "eagle-import:0207_10")
      (libsource (lib "eagle-import") (part "R-EU_0207/10"))
    )
    (comp (ref "R10")
      (value "680R")
      (footprint "eagle-import:0207_10")
      (libsource (lib "eagle-import") (part "resistor_348_R-EU_0207/10"))
    )
    (comp (ref "R11")
      (value "680R")
      (footprint "eagle-import:0207_10")
      (libsource (lib "eagle-import") (part "resistor_348_R-EU_0207/10"))
    )
    (comp (ref "R12")
      (value "680R")
      (footprint "eagle-import:0207_10")
      (libsource (lib "eagle-import") (part "resistor_348_R-EU_0207/10"))
    )
    (comp (ref "R13")
      (value "22k")
      (footprint "eagle-import:0207_10")
      (libsource (lib "eagle-import") (part "resistor_348_R-EU_0207/10"))
    )
    (comp (ref "S1")
      (value "10-XX")
      (footprint "eagle-import:B3F-10XX")
      (fields (field (name "MPN") "B3F-1000"))
      (libsource (lib "eagle-import") (part "10-XX"))
    )
    (comp (ref "S2")
      (value "10-XX")
      (footprint "eagle-import:B3F-10XX")
      (fields (field (name "MPN") "B3F-1000"))
      (libsource (lib "eagle-import") (part "10-XX"))
    )
    (comp (ref "S3")
      (value "10-XX")
      (footprint "eagle-import:B3F-10XX")
      (fields (field (name "MPN") "B3F-1000"))
      (libsource (lib "eagle-import") (part "10-XX"))
    )
    (comp (ref "SJ1") (value "SJ") (footprint "eagle-import:SJ") (libsource (lib "eagle-import") (part "SJ")))
    (comp (ref "X1")
      (value "ISA-SLOT")
      (footprint "eagle-import:ISA-8")
      (libsource (lib "eagle-import") (part "ISA-SLOT"))
    )
    (comp (ref "X2")
      (value "ISA-SLOT")
      (footprint "eagle-import:ISA-8")
      (libsource (lib "eagle-import") (part "ISA-SLOT"))
    )
    (comp (ref "X3")
      (value "ISA-SLOT")
      (footprint "eagle-import:ISA-8")
      (libsource (lib "eagle-import") (part "ISA-SLOT"))
    )
  )
  (nets
    (net (code "1") (name "+3V3") (class "Default")
      (node (ref "C4") (pin "+") (pinfunction "+_+") (pintype "passive"))
      (node (ref "IC1") (pin "2") (pinfunction "VOUT_2") (pintype "output"))
      (node (ref "R2") (pin "2") (pinfunction "2_2") (pintype "passive"))
    )
    (net (code "2") (name "+5V") (class "Default")
      (node (ref "C1") (pin "+") (pinfunction "+_+") (pintype "passive"))
      (node (ref "C10") (pin "1") (pinfunction "1_1") (pintype "passive"))
      (node (ref "C11") (pin "1") (pinfunction "1_1") (pintype "passive"))
      (node (ref "C12") (pin "1") (pinfunction "1_1") (pintype "passive"))
      (node (ref "C13") (pin "1") (pinfunction "1_1") (pintype "passive"))
      (node (ref "C14") (pin "1") (pinfunction "1_1") (pintype "passive"))
      (node (ref "C15") (pin "1") (pinfunction "1_1") (pintype "passive"))
      (node (ref "C17") (pin "2") (pinfunction "2_2") (pintype "passive"))
      (node (ref "C2") (pin "1") (pinfunction "1_1") (pintype "passive"))
      (node (ref "C20") (pin "1") (pinfunction "1_1") (pintype "passive"))
      (node (ref "C21") (pin "1") (pinfunction "1_1") (pintype "passive"))
      (node (ref "C22") (pin "1") (pinfunction "1_1") (pintype "passive"))
      (node (ref "C23") (pin "1") (pinfunction "1_1") (pintype "passive"))
      (node (ref "C3") (pin "+") (pinfunction "+_+") (pintype "passive"))
      (node (ref "C30") (pin "2") (pinfunction "2_2") (pintype "passive"))
      (node (ref "C31") (pin "2") (pinfunction "2_2") (pintype "passive"))
      (node (ref "C38") (pin "1") (pinfunction "1_1") (pintype "passive"))
      (node (ref "C5") (pin "1") (pinfunction "1_1") (pintype "passive"))
      (node (ref "C6") (pin "1") (pinfunction "1_1") (pintype "passive"))
      (node (ref "C7") (pin "1") (pinfunction "1_1") (pintype "passive"))
      (node (ref "C8") (pin "1") (pinfunction "1_1") (pintype "passive"))
      (node (ref "C9") (pin "2") (pinfunction "2_2") (pintype "passive"))
      (node (ref "IC1") (pin "3") (pinfunction "VIN_3") (pintype "input"))
      (node (ref "IC10") (pin "14") (pinfunction "VCC_14") (pintype "power_in"))
      (node (ref "IC11") (pin "16") (pinfunction "VCC_16") (pintype "power_in"))
      (node (ref "IC12") (pin "14") (pinfunction "VCC_14") (pintype "power_in"))
      (node (ref "IC14") (pin "15") (pinfunction "AVCC_15") (pintype "power_in"))
      (node (ref "IC14") (pin "5") (pinfunction "VCC_5") (pintype "power_in"))
      (node (ref "IC16") (pin "20") (pinfunction "VDD_20") (pintype "power_in"))
      (node (ref "IC17") (pin "16") (pinfunction "VCC_16") (pintype "power_in"))
      (node (ref "IC18") (pin "20") (pinfunction "VDD_20") (pintype "power_in"))
      (node (ref "IC19") (pin "15") (pinfunction "VCC_15") (pintype "power_in"))
      (node (ref "IC2") (pin "14") (pinfunction "VCC_14") (pintype "power_in"))
      (node (ref "IC20") (pin "18") (pinfunction "+5V_18") (pintype "bidirectional"))
      (node (ref "IC21") (pin "14") (pinfunction "VCC_14") (pintype "power_in"))
      (node (ref "IC3") (pin "14") (pinfunction "VCC_14") (pintype "power_in"))
      (node (ref "IC4") (pin "8") (pinfunction "VDD_8") (pintype "power_in"))
      (node (ref "IC5") (pin "27") (pinfunction "~{WE}_27") (pintype "input"))
      (node (ref "IC5") (pin "28") (pinfunction "VCC_28") (pintype "power_in"))
      (node (ref "IC6") (pin "28") (pinfunction "VCC_28") (pintype "power_in"))
      (node (ref "IC7") (pin "28") (pinfunction "VCC_28") (pintype "power_in"))
      (node (ref "IC8") (pin "3") (pinfunction "VCC_3") (pintype "bidirectional"))
      (node (ref "IC9") (pin "16") (pinfunction "VCC_16") (pintype "power_in"))
      (node (ref "J2") (pin "2") (pinfunction "2_2") (pintype "passive"))
      (node (ref "J3") (pin "7") (pinfunction "7_7") (pintype "passive"))
      (node (ref "JP1") (pin "2") (pinfunction "2_2") (pintype "passive"))
      (node (ref "JP10") (pin "1") (pinfunction "1_1") (pintype "passive"))
      (node (ref "JP10") (pin "2") (pinfunction "2_2") (pintype "passive"))
      (node (ref "JP11") (pin "4") (pinfunction "4_4") (pintype "passive"))
      (node (ref "JP8") (pin "1") (pinfunction "1_1") (pintype "passive"))
      (node (ref "JP8") (pin "2") (pinfunction "2_2") (pintype "passive"))
      (node (ref "L1") (pin "1") (pinfunction "1_1") (pintype "passive"))
      (node (ref "QG1") (pin "14") (pinfunction "VCC_14") (pintype "power_in"))
      (node (ref "R1") (pin "2") (pinfunction "2_2") (pintype "passive"))
      (node (ref "R10") (pin "2") (pinfunction "2_2") (pintype "passive"))
      (node (ref "R11") (pin "2") (pinfunction "2_2") (pintype "passive"))
      (node (ref "R12") (pin "2") (pinfunction "2_2") (pintype "passive"))
      (node (ref "R13") (pin "1") (pinfunction "1_1") (pintype "passive"))
      (node (ref "R14") (pin "1") (pinfunction "1_1") (pintype "passive"))
      (node (ref "R15") (pin "1") (pinfunction "1_1") (pintype "passive"))
      (node (ref "R16") (pin "2") (pinfunction "2_2") (pintype "passive"))
      (node (ref "R17") (pin "2") (pinfunction "2_2") (pintype "passive"))
      (node (ref "R20") (pin "1") (pinfunction "1_1") (pintype "passive"))
      (node (ref "R21") (pin "1") (pinfunction "1_1") (pintype "passive"))
      (node (ref "R3") (pin "1") (pinfunction "1_1") (pintype "passive"))
      (node (ref "R4") (pin "1") (pinfunction "1_1") (pintype "passive"))
      (node (ref "R5") (pin "1") (pinfunction "1_1") (pintype "passive"))
      (node (ref "R6") (pin "1") (pinfunction "1_1") (pintype "passive"))
      (node (ref "R7") (pin "1") (pinfunction "1_1") (pintype "passive"))
      (node (ref "R8") (pin "1") (pinfunction "1_1") (pintype "passive"))
      (node (ref "R9") (pin "1") (pinfunction "1_1") (pintype "passive"))
      (node (ref "RN1") (pin "1") (pinfunction "1_1") (pintype "passive"))
      (node (ref "RN2") (pin "1") (pinfunction "1_1") (pintype "passive"))
      (node (ref "X1") (pin "B29") (pinfunction "P_B29") (pintype "passive"))
      (node (ref "X1") (pin "B3") (pinfunction "P_B3") (pintype "passive"))
      (node (ref "X2") (pin "B29") (pinfunction "P_B29") (pintype "passive"))
      (node (ref "X2") (pin "B3") (pinfunction "P_B3") (pintype "passive"))
      (node (ref "X3") (pin "B29") (pinfunction "P_B29") (pintype "passive"))
      (node (ref "X3") (pin "B3") (pinfunction "P_B3") (pintype "passive"))
      (node (ref "X4") (pin "5") (pinfunction "5_5") (pintype "passive"))
    )
    (net (code "3") (name "2MHZ") (class "Default")
      (node (ref "IC3") (pin "9") (pinfunction "Q_9") (pintype "output"))
      (node (ref "JP5") (pin "1") (pinfunction "1_1") (pintype "passive"))
    )
    (net (code "4") (name "2PA0") (class "Default")
      (node (ref "IC14") (pin "20") (pinfunction "(PCINT0/ADC0)PA0_20") (pintype "bidirectional"))
      (node (ref "IC18") (pin "2") (pinfunction "PA0_2") (pintype "bidirectional"))
      (node (ref "JP10") (pin "3") (pinfunction "3_3") (pintype "passive"))
    )
    (net (code "5") (name "2PA1") (class "Default")
      (node (ref "IC14") (pin "19") (pinfunction "(PCINT1/ADC1)PA1_19") (pintype "bidirectional"))
      (node (ref "IC18") (pin "3") (pinfunction "PA1_3") (pintype "bidirectional"))
      (node (ref "JP10") (pin "5") (pinfunction "5_5") (pintype "passive"))
    )
    (net (code "6") (name "2PA2") (class "Default")
      (node (ref "IC14") (pin "18") (pinfunction "(PCINT2/ADC2)PA2_18") (pintype "bidirectional"))
      (node (ref "IC18") (pin "4") (pinfunction "PA2_4") (pintype "bidirectional"))
      (node (ref "JP10") (pin "7") (pinfunction "7_7") (pintype "passive"))
    )
    (net (code "7") (name "2PA3") (class "Default")
      (node (ref "IC14") (pin "17") (pinfunction "(PCINT3/AREF)PA3_17") (pintype "bidirectional"))
      (node (ref "IC18") (pin "5") (pinfunction "PA3_5") (pintype "bidirectional"))
      (node (ref "JP10") (pin "9") (pinfunction "9_9") (pintype "passive"))
    )
    (net (code "8") (name "2PA4") (class "Default")
      (node (ref "IC14") (pin "14") (pinfunction "(PCINT4/ADC3)PA4_14") (pintype "bidirectional"))
      (node (ref "IC18") (pin "6") (pinfunction "PA4_6") (pintype "bidirectional"))
      (node (ref "JP10") (pin "11") (pinfunction "11_11") (pintype "passive"))
    )
    (net (code "9") (name "2PA5") (class "Default")
      (node (ref "IC14") (pin "13") (pinfunction "(PCINT5/ADC4)PA5_13") (pintype "bidirectional"))
      (node (ref "IC18") (pin "7") (pinfunction "PA5_7") (pintype "bidirectional"))
      (node (ref "JP10") (pin "13") (pinfunction "13_13") (pintype "passive"))
    )
    (net (code "10") (name "2PA6") (class "Default")
      (node (ref "IC14") (pin "12") (pinfunction "(PCINT6/AIN0/ADC5)PA6_12") (pintype "bidirectional"))
      (node (ref "IC18") (pin "8") (pinfunction "PA6_8") (pintype "bidirectional"))
      (node (ref "JP10") (pin "15") (pinfunction "15_15") (pintype "passive"))
    )
    (net (code "11") (name "2PA7") (class "Default")
      (node (ref "IC14") (pin "11") (pinfunction "(PCINT7/AIN1/ADC6)PA7_11") (pintype "bidirectional"))
      (node (ref "IC18") (pin "9") (pinfunction "PA7_9") (pintype "bidirectional"))
      (node (ref "JP10") (pin "17") (pinfunction "17_17") (pintype "passive"))
    )
    (net (code "12") (name "2PB0") (class "Default")
      (node (ref "IC14") (pin "8") (pinfunction "PB5(ADC8/XTAL2/PCINT13)_8") (pintype "bidirectional"))
      (node (ref "IC18") (pin "10") (pinfunction "PB0_10") (pintype "bidirectional"))
      (node (ref "JP10") (pin "4") (pinfunction "4_4") (pintype "passive"))
    )
    (net (code "13") (name "2PB1") (class "Default")
      (node (ref "IC14") (pin "9") (pinfunction "PB6(ADC9/INT0/T0/PCINT14)_9") (pintype "bidirectional"))
      (node (ref "IC18") (pin "11") (pinfunction "PB1_11") (pintype "bidirectional"))
      (node (ref "JP10") (pin "6") (pinfunction "6_6") (pintype "passive"))
    )
    (net (code "14") (name "2PB2") (class "Default")
      (node (ref "C24") (pin "2") (pinfunction "2_2") (pintype "passive"))
      (node (ref "IC18") (pin "12") (pinfunction "PB2_12") (pintype "bidirectional"))
      (node (ref "J3") (pin "1") (pinfunction "1_1") (pintype "passive"))
      (node (ref "JP10") (pin "8") (pinfunction "8_8") (pintype "passive"))
      (node (ref "RN2") (pin "9") (pinfunction "9_9") (pintype "passive"))
    )
    (net (code "15") (name "2PB3") (class "Default")
      (node (ref "C26") (pin "2") (pinfunction "2_2") (pintype "passive"))
      (node (ref "IC18") (pin "13") (pinfunction "PB3_13") (pintype "bidirectional"))
      (node (ref "J3") (pin "2") (pinfunction "2_2") (pintype "passive"))
      (node (ref "JP10") (pin "10") (pinfunction "10_10") (pintype "passive"))
      (node (ref "RN2") (pin "8") (pinfunction "8_8") (pintype "passive"))
    )
    (net (code "16") (name "2PB4") (class "Default")
      (node (ref "C25") (pin "1") (pinfunction "1_1") (pintype "passive"))
      (node (ref "IC18") (pin "14") (pinfunction "PB4_14") (pintype "bidirectional"))
      (node (ref "J3") (pin "3") (pinfunction "3_3") (pintype "passive"))
      (node (ref "JP10") (pin "12") (pinfunction "12_12") (pintype "passive"))
      (node (ref "RN2") (pin "7") (pinfunction "7_7") (pintype "passive"))
    )
    (net (code "17") (name "2PB5") (class "Default")
      (node (ref "C27") (pin "1") (pinfunction "1_1") (pintype "passive"))
      (node (ref "IC18") (pin "15") (pinfunction "PB5_15") (pintype "bidirectional"))
      (node (ref "J3") (pin "4") (pinfunction "4_4") (pintype "passive"))
      (node (ref "JP10") (pin "14") (pinfunction "14_14") (pintype "passive"))
      (node (ref "RN2") (pin "6") (pinfunction "6_6") (pintype "passive"))
    )
    (net (code "18") (name "2PB6") (class "Default")
      (node (ref "C28") (pin "2") (pinfunction "2_2") (pintype "passive"))
      (node (ref "IC18") (pin "16") (pinfunction "PB6_16") (pintype "bidirectional"))
      (node (ref "J3") (pin "6") (pinfunction "6_6") (pintype "passive"))
      (node (ref "JP10") (pin "16") (pinfunction "16_16") (pintype "passive"))
      (node (ref "RN2") (pin "5") (pinfunction "5_5") (pintype "passive"))
    )
    (net (code "19") (name "2PB7") (class "Default")
      (node (ref "IC18") (pin "17") (pinfunction "PB7_17") (pintype "bidirectional"))
      (node (ref "JP10") (pin "18") (pinfunction "18_18") (pintype "passive"))
      (node (ref "RN2") (pin "4") (pinfunction "4_4") (pintype "passive"))
    )
    (net (code "20") (name "4MHZ") (class "Default")
      (node (ref "IC3") (pin "11") (pinfunction "CLK_11") (pintype "input"))
      (node (ref "IC3") (pin "5") (pinfunction "Q_5") (pintype "output"))
      (node (ref "JP4") (pin "1") (pinfunction "1_1") (pintype "passive"))
    )
    (net (code "21") (name "8MHZ") (class "Default")
      (node (ref "IC2") (pin "9") (pinfunction "Q_9") (pintype "output"))
      (node (ref "IC20") (pin "8") (pinfunction "CLK_8") (pintype "bidirectional"))
      (node (ref "IC3") (pin "3") (pinfunction "CLK_3") (pintype "input"))
      (node (ref "JP3") (pin "1") (pinfunction "1_1") (pintype "passive"))
    )
    (net (code "22") (name "16MHZ") (class "Default")
      (node (ref "IC2") (pin "11") (pinfunction "CLK_11") (pintype "input"))
      (node (ref "IC2") (pin "5") (pinfunction "Q_5") (pintype "output"))
      (node (ref "JP2") (pin "1") (pinfunction "1_1") (pintype "passive"))
    )
    (net (code "23") (name "32MHZ") (class "Default")
      (node (ref "IC2") (pin "3") (pinfunction "CLK_3") (pintype "input"))
      (node (ref "QG1") (pin "8") (pinfunction "OUT_8") (pintype "output"))
      (node (ref "X1") (pin "B18") (pinfunction "P_B18") (pintype "passive"))
      (node (ref "X2") (pin "B18") (pinfunction "P_B18") (pintype "passive"))
      (node (ref "X3") (pin "B18") (pinfunction "P_B18") (pintype "passive"))
    )
    (net (code "24") (name "A0") (class "Default")
      (node (ref "IC16") (pin "38") (pinfunction "RS0_38") (pintype "input"))
      (node (ref "IC18") (pin "38") (pinfunction "RS0_38") (pintype "input"))
      (node (ref "IC19") (pin "13") (pinfunction "RS0_13") (pintype "input"))
      (node (ref "IC20") (pin "3") (pinfunction "A0_3") (pintype "bidirectional"))
      (node (ref "IC4") (pin "9") (pinfunction "A0_9") (pintype "bidirectional"))
      (node (ref "IC5") (pin "10") (pinfunction "A0_10") (pintype "input"))
      (node (ref "IC6") (pin "10") (pinfunction "A0_10") (pintype "input"))
      (node (ref "IC7") (pin "10") (pinfunction "A0_10") (pintype "input"))
      (node (ref "X1") (pin "A31") (pinfunction "P_A31") (pintype "passive"))
      (node (ref "X2") (pin "A31") (pinfunction "P_A31") (pintype "passive"))
      (node (ref "X3") (pin "A31") (pinfunction "P_A31") (pintype "passive"))
    )
    (net (code "25") (name "A1") (class "Default")
      (node (ref "IC16") (pin "37") (pinfunction "RS1_37") (pintype "input"))
      (node (ref "IC18") (pin "37") (pinfunction "RS1_37") (pintype "input"))
      (node (ref "IC19") (pin "14") (pinfunction "RS1_14") (pintype "input"))
      (node (ref "IC4") (pin "10") (pinfunction "A1_10") (pintype "bidirectional"))
      (node (ref "IC5") (pin "9") (pinfunction "A1_9") (pintype "input"))
      (node (ref "IC6") (pin "9") (pinfunction "A1_9") (pintype "input"))
      (node (ref "IC7") (pin "9") (pinfunction "A1_9") (pintype "input"))
      (node (ref "X1") (pin "A30") (pinfunction "P_A30") (pintype "passive"))
      (node (ref "X2") (pin "A30") (pinfunction "P_A30") (pintype "passive"))
      (node (ref "X3") (pin "A30") (pinfunction "P_A30") (pintype "passive"))
    )
    (net (code "26") (name "A2") (class "Default")
      (node (ref "IC16") (pin "36") (pinfunction "RS2_36") (pintype "input"))
      (node (ref "IC18") (pin "36") (pinfunction "RS2_36") (pintype "input"))
      (node (ref "IC4") (pin "11") (pinfunction "A2_11") (pintype "bidirectional"))
      (node (ref "IC5") (pin "8") (pinfunction "A2_8") (pintype "input"))
      (node (ref "IC6") (pin "8") (pinfunction "A2_8") (pintype "input"))
      (node (ref "IC7") (pin "8") (pinfunction "A2_8") (pintype "input"))
      (node (ref "X1") (pin "A29") (pinfunction "P_A29") (pintype "passive"))
      (node (ref "X2") (pin "A29") (pinfunction "P_A29") (pintype "passive"))
      (node (ref "X3") (pin "A29") (pinfunction "P_A29") (pintype "passive"))
    )
    (net (code "27") (name "A3") (class "Default")
      (node (ref "IC16") (pin "35") (pinfunction "RS3_35") (pintype "input"))
      (node (ref "IC18") (pin "35") (pinfunction "RS3_35") (pintype "input"))
      (node (ref "IC4") (pin "12") (pinfunction "A3_12") (pintype "bidirectional"))
      (node (ref "IC5") (pin "7") (pinfunction "A3_7") (pintype "input"))
      (node (ref "IC6") (pin "7") (pinfunction "A3_7") (pintype "input"))
      (node (ref "IC7") (pin "7") (pinfunction "A3_7") (pintype "input"))
      (node (ref "X1") (pin "A28") (pinfunction "P_A28") (pintype "passive"))
      (node (ref "X2") (pin "A28") (pinfunction "P_A28") (pintype "passive"))
      (node (ref "X3") (pin "A28") (pinfunction "P_A28") (pintype "passive"))
    )
    (net (code "28") (name "A4") (class "Default")
      (node (ref "IC4") (pin "13") (pinfunction "A4_13") (pintype "bidirectional"))
      (node (ref "IC5") (pin "6") (pinfunction "A4_6") (pintype "input"))
      (node (ref "IC6") (pin "6") (pinfunction "A4_6") (pintype "input"))
      (node (ref "IC7") (pin "6") (pinfunction "A4_6") (pintype "input"))
      (node (ref "X1") (pin "A27") (pinfunction "P_A27") (pintype "passive"))
      (node (ref "X2") (pin "A27") (pinfunction "P_A27") (pintype "passive"))
      (node (ref "X3") (pin "A27") (pinfunction "P_A27") (pintype "passive"))
    )
    (net (code "29") (name "A5") (class "Default")
      (node (ref "IC4") (pin "14") (pinfunction "A5_14") (pintype "bidirectional"))
      (node (ref "IC5") (pin "5") (pinfunction "A5_5") (pintype "input"))
      (node (ref "IC6") (pin "5") (pinfunction "A5_5") (pintype "input"))
      (node (ref "IC7") (pin "5") (pinfunction "A5_5") (pintype "input"))
      (node (ref "X1") (pin "A26") (pinfunction "P_A26") (pintype "passive"))
      (node (ref "X2") (pin "A26") (pinfunction "P_A26") (pintype "passive"))
      (node (ref "X3") (pin "A26") (pinfunction "P_A26") (pintype "passive"))
    )
    (net (code "30") (name "A6") (class "Default")
      (node (ref "IC4") (pin "15") (pinfunction "A6_15") (pintype "bidirectional"))
      (node (ref "IC5") (pin "4") (pinfunction "A6_4") (pintype "input"))
      (node (ref "IC6") (pin "4") (pinfunction "A6_4") (pintype "input"))
      (node (ref "IC7") (pin "4") (pinfunction "A6_4") (pintype "input"))
      (node (ref "X1") (pin "A25") (pinfunction "P_A25") (pintype "passive"))
      (node (ref "X2") (pin "A25") (pinfunction "P_A25") (pintype "passive"))
      (node (ref "X3") (pin "A25") (pinfunction "P_A25") (pintype "passive"))
    )
    (net (code "31") (name "A7") (class "Default")
      (node (ref "IC10") (pin "4") (pinfunction "I0_4") (pintype "input"))
      (node (ref "IC10") (pin "5") (pinfunction "I1_5") (pintype "input"))
      (node (ref "IC16") (pin "24") (pinfunction "CS1_24") (pintype "input"))
      (node (ref "IC4") (pin "16") (pinfunction "A7_16") (pintype "bidirectional"))
      (node (ref "IC5") (pin "3") (pinfunction "A7_3") (pintype "input"))
      (node (ref "IC6") (pin "3") (pinfunction "A7_3") (pintype "input"))
      (node (ref "IC7") (pin "3") (pinfunction "A7_3") (pintype "input"))
      (node (ref "X1") (pin "A24") (pinfunction "P_A24") (pintype "passive"))
      (node (ref "X2") (pin "A24") (pinfunction "P_A24") (pintype "passive"))
      (node (ref "X3") (pin "A24") (pinfunction "P_A24") (pintype "passive"))
    )
    (net (code "32") (name "A8") (class "Default")
      (node (ref "IC4") (pin "17") (pinfunction "A8_17") (pintype "bidirectional"))
      (node (ref "IC5") (pin "25") (pinfunction "A8_25") (pintype "input"))
      (node (ref "IC6") (pin "25") (pinfunction "A8_25") (pintype "input"))
      (node (ref "IC7") (pin "25") (pinfunction "A8_25") (pintype "input"))
      (node (ref "IC9") (pin "14") (pinfunction "A_14") (pintype "input"))
      (node (ref "X1") (pin "A23") (pinfunction "P_A23") (pintype "passive"))
      (node (ref "X2") (pin "A23") (pinfunction "P_A23") (pintype "passive"))
      (node (ref "X3") (pin "A23") (pinfunction "P_A23") (pintype "passive"))
    )
    (net (code "33") (name "A9") (class "Default")
      (node (ref "IC4") (pin "18") (pinfunction "A9_18") (pintype "bidirectional"))
      (node (ref "IC5") (pin "24") (pinfunction "A9_24") (pintype "input"))
      (node (ref "IC6") (pin "24") (pinfunction "A9_24") (pintype "input"))
      (node (ref "IC7") (pin "24") (pinfunction "A9_24") (pintype "input"))
      (node (ref "IC9") (pin "13") (pinfunction "B_13") (pintype "input"))
      (node (ref "X1") (pin "A22") (pinfunction "P_A22") (pintype "passive"))
      (node (ref "X2") (pin "A22") (pinfunction "P_A22") (pintype "passive"))
      (node (ref "X3") (pin "A22") (pinfunction "P_A22") (pintype "passive"))
    )
    (net (code "34") (name "A10") (class "Default")
      (node (ref "IC4") (pin "19") (pinfunction "A10_19") (pintype "bidirectional"))
      (node (ref "IC5") (pin "21") (pinfunction "A10_21") (pintype "input"))
      (node (ref "IC6") (pin "21") (pinfunction "A10_21") (pintype "input"))
      (node (ref "IC7") (pin "21") (pinfunction "A10_21") (pintype "input"))
      (node (ref "IC9") (pin "2") (pinfunction "A_2") (pintype "input"))
      (node (ref "X1") (pin "A21") (pinfunction "P_A21") (pintype "passive"))
      (node (ref "X2") (pin "A21") (pinfunction "P_A21") (pintype "passive"))
      (node (ref "X3") (pin "A21") (pinfunction "P_A21") (pintype "passive"))
    )
    (net (code "35") (name "A11") (class "Default")
      (node (ref "IC4") (pin "20") (pinfunction "A11_20") (pintype "bidirectional"))
      (node (ref "IC5") (pin "23") (pinfunction "A11_23") (pintype "input"))
      (node (ref "IC6") (pin "23") (pinfunction "A11_23") (pintype "input"))
      (node (ref "IC7") (pin "23") (pinfunction "A11_23") (pintype "input"))
      (node (ref "IC9") (pin "3") (pinfunction "B_3") (pintype "input"))
      (node (ref "X1") (pin "A20") (pinfunction "P_A20") (pintype "passive"))
      (node (ref "X2") (pin "A20") (pinfunction "P_A20") (pintype "passive"))
      (node (ref "X3") (pin "A20") (pinfunction "P_A20") (pintype "passive"))
    )
    (net (code "36") (name "A12") (class "Default")
      (node (ref "IC11") (pin "14") (pinfunction "A_14") (pintype "input"))
      (node (ref "IC4") (pin "22") (pinfunction "A12_22") (pintype "bidirectional"))
      (node (ref "IC5") (pin "2") (pinfunction "A12_2") (pintype "input"))
      (node (ref "IC6") (pin "2") (pinfunction "A12_2") (pintype "input"))
      (node (ref "IC7") (pin "2") (pinfunction "A12_2") (pintype "input"))
      (node (ref "X1") (pin "A19") (pinfunction "P_A19") (pintype "passive"))
      (node (ref "X2") (pin "A19") (pinfunction "P_A19") (pintype "passive"))
      (node (ref "X3") (pin "A19") (pinfunction "P_A19") (pintype "passive"))
    )
    (net (code "37") (name "A13") (class "Default")
      (node (ref "IC11") (pin "13") (pinfunction "B_13") (pintype "input"))
      (node (ref "IC12") (pin "4") (pinfunction "I0_4") (pintype "input"))
      (node (ref "IC4") (pin "23") (pinfunction "A13_23") (pintype "bidirectional"))
      (node (ref "IC6") (pin "26") (pinfunction "A13_26") (pintype "input"))
      (node (ref "IC7") (pin "26") (pinfunction "A13_26") (pintype "input"))
      (node (ref "X1") (pin "A18") (pinfunction "P_A18") (pintype "passive"))
      (node (ref "X2") (pin "A18") (pinfunction "P_A18") (pintype "passive"))
      (node (ref "X3") (pin "A18") (pinfunction "P_A18") (pintype "passive"))
    )
    (net (code "38") (name "A14") (class "Default")
      (node (ref "IC11") (pin "2") (pinfunction "A_2") (pintype "input"))
      (node (ref "IC4") (pin "24") (pinfunction "A14_24") (pintype "bidirectional"))
      (node (ref "IC6") (pin "1") (pinfunction "A14_1") (pintype "input"))
      (node (ref "X1") (pin "A17") (pinfunction "P_A17") (pintype "passive"))
      (node (ref "X2") (pin "A17") (pinfunction "P_A17") (pintype "passive"))
      (node (ref "X3") (pin "A17") (pinfunction "P_A17") (pintype "passive"))
    )
    (net (code "39") (name "A15") (class "Default")
      (node (ref "IC11") (pin "3") (pinfunction "B_3") (pintype "input"))
      (node (ref "IC4") (pin "25") (pinfunction "A15_25") (pintype "bidirectional"))
      (node (ref "IC6") (pin "20") (pinfunction "~{CS}_20") (pintype "input"))
      (node (ref "X1") (pin "A16") (pinfunction "P_A16") (pintype "passive"))
      (node (ref "X2") (pin "A16") (pinfunction "P_A16") (pintype "passive"))
      (node (ref "X3") (pin "A16") (pinfunction "P_A16") (pintype "passive"))
    )
    (net (code "40") (name "ACIA_CSH") (class "Default")
      (node (ref "IC19") (pin "2") (pinfunction "CS0_2") (pintype "input"))
      (node (ref "R17") (pin "1") (pinfunction "1_1") (pintype "passive"))
    )
    (net (code "41") (name "AVR_RST") (class "Default")
      (node (ref "IC14") (pin "10") (pinfunction "PB7(ADC10/~{RESET}/PCINT15)_10") (pintype "bidirectional"))
      (node (ref "J2") (pin "5") (pinfunction "5_5") (pintype "passive"))
    )
    (net (code "42") (name "BE") (class "Default")
      (node (ref "IC4") (pin "36") (pinfunction "BE_36") (pintype "input"))
      (node (ref "R9") (pin "2") (pinfunction "2_2") (pintype "passive"))
      (node (ref "X1") (pin "A11") (pinfunction "P_A11") (pintype "passive"))
      (node (ref "X2") (pin "A11") (pinfunction "P_A11") (pintype "passive"))
      (node (ref "X3") (pin "A11") (pinfunction "P_A11") (pintype "passive"))
    )
    (net (code "43") (name "C-F") (class "Default")
      (node (ref "IC12") (pin "3") (pinfunction "O_3") (pintype "output"))
      (node (ref "IC12") (pin "5") (pinfunction "I1_5") (pintype "input"))
    )
    (net (code "44") (name "CA1") (class "Default")
      (node (ref "IC16") (pin "40") (pinfunction "CA1_40") (pintype "bidirectional"))
      (node (ref "JP9") (pin "1") (pinfunction "1_1") (pintype "passive"))
    )
    (net (code "45") (name "CA2") (class "Default")
      (node (ref "IC16") (pin "39") (pinfunction "CA2_39") (pintype "bidirectional"))
      (node (ref "JP9") (pin "3") (pinfunction "3_3") (pintype "passive"))
    )
    (net (code "46") (name "CB1") (class "Default")
      (node (ref "IC16") (pin "18") (pinfunction "CB1_18") (pintype "bidirectional"))
      (node (ref "JP9") (pin "2") (pinfunction "2_2") (pintype "passive"))
    )
    (net (code "47") (name "CB2") (class "Default")
      (node (ref "IC16") (pin "19") (pinfunction "CB2_19") (pintype "bidirectional"))
      (node (ref "JP9") (pin "4") (pinfunction "4_4") (pintype "passive"))
    )
    (net (code "48") (name "CLK") (class "Default")
      (node (ref "IC4") (pin "37") (pinfunction "PH0-IN_37") (pintype "input"))
      (node (ref "JP13") (pin "1") (pinfunction "1_1") (pintype "passive"))
      (node (ref "X1") (pin "B30") (pinfunction "P_B30") (pintype "passive"))
      (node (ref "X2") (pin "B30") (pinfunction "P_B30") (pintype "passive"))
      (node (ref "X3") (pin "B30") (pinfunction "P_B30") (pintype "passive"))
    )
    (net (code "49") (name "CTS") (class "Default")
      (node (ref "IC19") (pin "9") (pinfunction "CTS_9") (pintype "input"))
      (node (ref "JP11") (pin "7") (pinfunction "7_7") (pintype "passive"))
      (node (ref "JP12") (pin "2") (pinfunction "2_2") (pintype "passive"))
      (node (ref "SJ2") (pin "2") (pinfunction "2_2") (pintype "passive"))
    )
    (net (code "50") (name "D0") (class "Default")
      (node (ref "IC16") (pin "33") (pinfunction "D0_33") (pintype "bidirectional"))
      (node (ref "IC18") (pin "33") (pinfunction "D0_33") (pintype "bidirectional"))
      (node (ref "IC19") (pin "18") (pinfunction "D0_18") (pintype "bidirectional"))
      (node (ref "IC20") (pin "10") (pinfunction "D0_10") (pintype "bidirectional"))
      (node (ref "IC4") (pin "33") (pinfunction "D0_33") (pintype "bidirectional"))
      (node (ref "IC5") (pin "11") (pinfunction "D0_11") (pintype "tri_state"))
      (node (ref "IC6") (pin "11") (pinfunction "I/O0_11") (pintype "bidirectional"))
      (node (ref "IC7") (pin "11") (pinfunction "I/O0_11") (pintype "bidirectional"))
      (node (ref "X1") (pin "A9") (pinfunction "P_A9") (pintype "passive"))
      (node (ref "X2") (pin "A9") (pinfunction "P_A9") (pintype "passive"))
      (node (ref "X3") (pin "A9") (pinfunction "P_A9") (pintype "passive"))
    )
    (net (code "51") (name "D1") (class "Default")
      (node (ref "IC16") (pin "32") (pinfunction "D1_32") (pintype "bidirectional"))
      (node (ref "IC18") (pin "32") (pinfunction "D1_32") (pintype "bidirectional"))
      (node (ref "IC19") (pin "19") (pinfunction "D1_19") (pintype "bidirectional"))
      (node (ref "IC20") (pin "11") (pinfunction "D1_11") (pintype "bidirectional"))
      (node (ref "IC4") (pin "32") (pinfunction "D1_32") (pintype "bidirectional"))
      (node (ref "IC5") (pin "12") (pinfunction "D1_12") (pintype "tri_state"))
      (node (ref "IC6") (pin "12") (pinfunction "I/O1_12") (pintype "bidirectional"))
      (node (ref "IC7") (pin "12") (pinfunction "I/O1_12") (pintype "bidirectional"))
      (node (ref "X1") (pin "A8") (pinfunction "P_A8") (pintype "passive"))
      (node (ref "X2") (pin "A8") (pinfunction "P_A8") (pintype "passive"))
      (node (ref "X3") (pin "A8") (pinfunction "P_A8") (pintype "passive"))
    )
    (net (code "52") (name "D2") (class "Default")
      (node (ref "IC16") (pin "31") (pinfunction "D2_31") (pintype "bidirectional"))
      (node (ref "IC18") (pin "31") (pinfunction "D2_31") (pintype "bidirectional"))
      (node (ref "IC19") (pin "20") (pinfunction "D2_20") (pintype "bidirectional"))
      (node (ref "IC20") (pin "12") (pinfunction "D2_12") (pintype "bidirectional"))
      (node (ref "IC4") (pin "31") (pinfunction "D2_31") (pintype "bidirectional"))
      (node (ref "IC5") (pin "13") (pinfunction "D2_13") (pintype "tri_state"))
      (node (ref "IC6") (pin "13") (pinfunction "I/O2_13") (pintype "bidirectional"))
      (node (ref "IC7") (pin "13") (pinfunction "I/O2_13") (pintype "bidirectional"))
      (node (ref "X1") (pin "A7") (pinfunction "P_A7") (pintype "passive"))
      (node (ref "X2") (pin "A7") (pinfunction "P_A7") (pintype "passive"))
      (node (ref "X3") (pin "A7") (pinfunction "P_A7") (pintype "passive"))
    )
    (net (code "53") (name "D3") (class "Default")
      (node (ref "IC16") (pin "30") (pinfunction "D3_30") (pintype "bidirectional"))
      (node (ref "IC18") (pin "30") (pinfunction "D3_30") (pintype "bidirectional"))
      (node (ref "IC19") (pin "21") (pinfunction "D3_21") (pintype "bidirectional"))
      (node (ref "IC20") (pin "13") (pinfunction "D3_13") (pintype "bidirectional"))
      (node (ref "IC4") (pin "30") (pinfunction "D3_30") (pintype "bidirectional"))
      (node (ref "IC5") (pin "15") (pinfunction "D3_15") (pintype "tri_state"))
      (node (ref "IC6") (pin "15") (pinfunction "I/O3_15") (pintype "bidirectional"))
      (node (ref "IC7") (pin "15") (pinfunction "I/O3_15") (pintype "bidirectional"))
      (node (ref "X1") (pin "A6") (pinfunction "P_A6") (pintype "passive"))
      (node (ref "X2") (pin "A6") (pinfunction "P_A6") (pintype "passive"))
      (node (ref "X3") (pin "A6") (pinfunction "P_A6") (pintype "passive"))
    )
    (net (code "54") (name "D4") (class "Default")
      (node (ref "IC16") (pin "29") (pinfunction "D4_29") (pintype "bidirectional"))
      (node (ref "IC18") (pin "29") (pinfunction "D4_29") (pintype "bidirectional"))
      (node (ref "IC19") (pin "22") (pinfunction "D4_22") (pintype "bidirectional"))
      (node (ref "IC20") (pin "14") (pinfunction "D4_14") (pintype "bidirectional"))
      (node (ref "IC4") (pin "29") (pinfunction "D4_29") (pintype "bidirectional"))
      (node (ref "IC5") (pin "16") (pinfunction "D4_16") (pintype "tri_state"))
      (node (ref "IC6") (pin "16") (pinfunction "I/O4_16") (pintype "bidirectional"))
      (node (ref "IC7") (pin "16") (pinfunction "I/O4_16") (pintype "bidirectional"))
      (node (ref "X1") (pin "A5") (pinfunction "P_A5") (pintype "passive"))
      (node (ref "X2") (pin "A5") (pinfunction "P_A5") (pintype "passive"))
      (node (ref "X3") (pin "A5") (pinfunction "P_A5") (pintype "passive"))
    )
    (net (code "55") (name "D5") (class "Default")
      (node (ref "IC16") (pin "28") (pinfunction "D5_28") (pintype "bidirectional"))
      (node (ref "IC18") (pin "28") (pinfunction "D5_28") (pintype "bidirectional"))
      (node (ref "IC19") (pin "23") (pinfunction "D5_23") (pintype "bidirectional"))
      (node (ref "IC20") (pin "15") (pinfunction "D5_15") (pintype "bidirectional"))
      (node (ref "IC4") (pin "28") (pinfunction "D5_28") (pintype "bidirectional"))
      (node (ref "IC5") (pin "17") (pinfunction "D5_17") (pintype "tri_state"))
      (node (ref "IC6") (pin "17") (pinfunction "I/O5_17") (pintype "bidirectional"))
      (node (ref "IC7") (pin "17") (pinfunction "I/O5_17") (pintype "bidirectional"))
      (node (ref "X1") (pin "A4") (pinfunction "P_A4") (pintype "passive"))
      (node (ref "X2") (pin "A4") (pinfunction "P_A4") (pintype "passive"))
      (node (ref "X3") (pin "A4") (pinfunction "P_A4") (pintype "passive"))
    )
    (net (code "56") (name "D6") (class "Default")
      (node (ref "IC16") (pin "27") (pinfunction "D6_27") (pintype "bidirectional"))
      (node (ref "IC18") (pin "27") (pinfunction "D6_27") (pintype "bidirectional"))
      (node (ref "IC19") (pin "24") (pinfunction "D6_24") (pintype "bidirectional"))
      (node (ref "IC20") (pin "16") (pinfunction "D6_16") (pintype "bidirectional"))
      (node (ref "IC4") (pin "27") (pinfunction "D6_27") (pintype "bidirectional"))
      (node (ref "IC5") (pin "18") (pinfunction "D6_18") (pintype "tri_state"))
      (node (ref "IC6") (pin "18") (pinfunction "I/O6_18") (pintype "bidirectional"))
      (node (ref "IC7") (pin "18") (pinfunction "I/O6_18") (pintype "bidirectional"))
      (node (ref "X1") (pin "A3") (pinfunction "P_A3") (pintype "passive"))
      (node (ref "X2") (pin "A3") (pinfunction "P_A3") (pintype "passive"))
      (node (ref "X3") (pin "A3") (pinfunction "P_A3") (pintype "passive"))
    )
    (net (code "57") (name "D7") (class "Default")
      (node (ref "IC16") (pin "26") (pinfunction "D7_26") (pintype "bidirectional"))
      (node (ref "IC18") (pin "26") (pinfunction "D7_26") (pintype "bidirectional"))
      (node (ref "IC19") (pin "25") (pinfunction "D7_25") (pintype "bidirectional"))
      (node (ref "IC20") (pin "17") (pinfunction "D7_17") (pintype "bidirectional"))
      (node (ref "IC4") (pin "26") (pinfunction "D7_26") (pintype "bidirectional"))
      (node (ref "IC5") (pin "19") (pinfunction "D7_19") (pintype "tri_state"))
      (node (ref "IC6") (pin "19") (pinfunction "I/O7_19") (pintype "bidirectional"))
      (node (ref "IC7") (pin "19") (pinfunction "I/O7_19") (pintype "bidirectional"))
      (node (ref "X1") (pin "A2") (pinfunction "P_A2") (pintype "passive"))
      (node (ref "X2") (pin "A2") (pinfunction "P_A2") (pintype "passive"))
      (node (ref "X3") (pin "A2") (pinfunction "P_A2") (pintype "passive"))
    )
    (net (code "58") (name "DTR") (class "Default")
      (node (ref "JP11") (pin "1") (pinfunction "1_1") (pintype "passive"))
      (node (ref "SJ1") (pin "2") (pinfunction "2_2") (pintype "passive"))
    )
    (net (code "59") (name "E-F") (class "Default")
      (node (ref "IC12") (pin "12") (pinfunction "I0_12") (pintype "input"))
      (node (ref "IC12") (pin "8") (pinfunction "O_8") (pintype "output"))
    )
    (net (code "60") (name "GND") (class "Default")
      (node (ref "C1") (pin "-") (pinfunction "-_-") (pintype "passive"))
      (node (ref "C10") (pin "2") (pinfunction "2_2") (pintype "passive"))
      (node (ref "C11") (pin "2") (pinfunction "2_2") (pintype "passive"))
      (node (ref "C12") (pin "2") (pinfunction "2_2") (pintype "passive"))
      (node (ref "C13") (pin "2") (pinfunction "2_2") (pintype "passive"))
      (node (ref "C14") (pin "2") (pinfunction "2_2") (pintype "passive"))
      (node (ref "C15") (pin "2") (pinfunction "2_2") (pintype "passive"))
      (node (ref "C17") (pin "1") (pinfunction "1_1") (pintype "passive"))
      (node (ref "C2") (pin "2") (pinfunction "2_2") (pintype "passive"))
      (node (ref "C20") (pin "2") (pinfunction "2_2") (pintype "passive"))
      (node (ref "C21") (pin "2") (pinfunction "2_2") (pintype "passive"))
      (node (ref "C22") (pin "2") (pinfunction "2_2") (pintype "passive"))
      (node (ref "C23") (pin "2") (pinfunction "2_2") (pintype "passive"))
      (node (ref "C24") (pin "1") (pinfunction "1_1") (pintype "passive"))
      (node (ref "C25") (pin "2") (pinfunction "2_2") (pintype "passive"))
      (node (ref "C26") (pin "1") (pinfunction "1_1") (pintype "passive"))
      (node (ref "C27") (pin "2") (pinfunction "2_2") (pintype "passive"))
      (node (ref "C28") (pin "1") (pinfunction "1_1") (pintype "passive"))
      (node (ref "C29") (pin "1") (pinfunction "1_1") (pintype "passive"))
      (node (ref "C3") (pin "-") (pinfunction "-_-") (pintype "passive"))
      (node (ref "C30") (pin "1") (pinfunction "1_1") (pintype "passive"))
      (node (ref "C31") (pin "1") (pinfunction "1_1") (pintype "passive"))
      (node (ref "C32") (pin "1") (pinfunction "1_1") (pintype "passive"))
      (node (ref "C33") (pin "1") (pinfunction "1_1") (pintype "passive"))
      (node (ref "C34") (pin "1") (pinfunction "1_1") (pintype "passive"))
      (node (ref "C35") (pin "1") (pinfunction "1_1") (pintype "passive"))
      (node (ref "C38") (pin "2") (pinfunction "2_2") (pintype "passive"))
      (node (ref "C4") (pin "-") (pinfunction "-_-") (pintype "passive"))
      (node (ref "C5") (pin "2") (pinfunction "2_2") (pintype "passive"))
      (node (ref "C6") (pin "2") (pinfunction "2_2") (pintype "passive"))
      (node (ref "C7") (pin "2") (pinfunction "2_2") (pintype "passive"))
      (node (ref "C8") (pin "2") (pinfunction "2_2") (pintype "passive"))
      (node (ref "C9") (pin "1") (pinfunction "1_1") (pintype "passive"))
      (node (ref "IC1") (pin "1") (pinfunction "GND_1") (pintype "power_in"))
      (node (ref "IC10") (pin "7") (pinfunction "GND_7") (pintype "power_in"))
      (node (ref "IC11") (pin "1") (pinfunction "G_1") (pintype "input"))
      (node (ref "IC11") (pin "8") (pinfunction "GND_8") (pintype "power_in"))
      (node (ref "IC12") (pin "7") (pinfunction "GND_7") (pintype "power_in"))
      (node (ref "IC14") (pin "16") (pinfunction "GND_16") (pintype "power_in"))
      (node (ref "IC14") (pin "6") (pinfunction "GND_6") (pintype "power_in"))
      (node (ref "IC16") (pin "1") (pinfunction "VSS_1") (pintype "power_in"))
      (node (ref "IC17") (pin "5") (pinfunction "EI_5") (pintype "input"))
      (node (ref "IC17") (pin "8") (pinfunction "GND_8") (pintype "power_in"))
      (node (ref "IC18") (pin "1") (pinfunction "VSS_1") (pintype "power_in"))
      (node (ref "IC19") (pin "1") (pinfunction "GND_1") (pintype "power_in"))
      (node (ref "IC19") (pin "16") (pinfunction "DCD_16") (pintype "input"))
      (node (ref "IC19") (pin "17") (pinfunction "DSR_17") (pintype "input"))
      (node (ref "IC2") (pin "7") (pinfunction "GND_7") (pintype "power_in"))
      (node (ref "IC20") (pin "9") (pinfunction "GND_9") (pintype "bidirectional"))
      (node (ref "IC21") (pin "7") (pinfunction "GND_7") (pintype "power_in"))
      (node (ref "IC3") (pin "7") (pinfunction "GND_7") (pintype "power_in"))
      (node (ref "IC4") (pin "21") (pinfunction "VSS_21") (pintype "power_in"))
      (node (ref "IC5") (pin "14") (pinfunction "GND_14") (pintype "power_in"))
      (node (ref "IC6") (pin "14") (pinfunction "VSS_14") (pintype "power_in"))
      (node (ref "IC7") (pin "1") (pinfunction "A14_1") (pintype "input"))
      (node (ref "IC7") (pin "14") (pinfunction "VSS_14") (pintype "power_in"))
      (node (ref "IC8") (pin "2") (pinfunction "GND_2") (pintype "bidirectional"))
      (node (ref "IC8") (pin "4") (pinfunction "GND_4") (pintype "bidirectional"))
      (node (ref "IC9") (pin "8") (pinfunction "GND_8") (pintype "power_in"))
      (node (ref "J1") (pin "2") (pinfunction "2_2") (pintype "passive"))
      (node (ref "J1") (pin "3") (pinfunction "3_3") (pintype "passive"))
      (node (ref "J2") (pin "6") (pinfunction "6_6") (pintype "passive"))
      (node (ref "J3") (pin "8") (pinfunction "8_8") (pintype "passive"))
      (node (ref "JP10") (pin "19") (pinfunction "19_19") (pintype "passive"))
      (node (ref "JP10") (pin "20") (pinfunction "20_20") (pintype "passive"))
      (node (ref "JP11") (pin "6") (pinfunction "6_6") (pintype "passive"))
      (node (ref "JP6") (pin "1") (pinfunction "1_1") (pintype "passive"))
      (node (ref "JP8") (pin "19") (pinfunction "19_19") (pintype "passive"))
      (node (ref "JP8") (pin "20") (pinfunction "20_20") (pintype "passive"))
      (node (ref "LED1") (pin "K") (pinfunction "C_K") (pintype "passive"))
      (node (ref "LED2") (pin "K") (pinfunction "C_K") (pintype "passive"))
      (node (ref "QG1") (pin "7") (pinfunction "GND_7") (pintype "power_in"))
      (node (ref "S1") (pin "1") (pinfunction "S_1") (pintype "passive"))
      (node (ref "S1") (pin "2") (pinfunction "S1_2") (pintype "passive"))
      (node (ref "S2") (pin "1") (pinfunction "S_1") (pintype "passive"))
      (node (ref "S2") (pin "2") (pinfunction "S1_2") (pintype "passive"))
      (node (ref "S3") (pin "1") (pinfunction "S_1") (pintype "passive"))
      (node (ref "S3") (pin "2") (pinfunction "S1_2") (pintype "passive"))
      (node (ref "SJ2") (pin "1") (pinfunction "1_1") (pintype "passive"))
      (node (ref "X1") (pin "B1") (pinfunction "P_B1") (pintype "passive"))
      (node (ref "X1") (pin "B31") (pinfunction "P_B31") (pintype "passive"))
      (node (ref "X2") (pin "B1") (pinfunction "P_B1") (pintype "passive"))
      (node (ref "X2") (pin "B31") (pinfunction "P_B31") (pintype "passive"))
      (node (ref "X3") (pin "B1") (pinfunction "P_B1") (pintype "passive"))
      (node (ref "X3") (pin "B31") (pinfunction "P_B31") (pintype "passive"))
      (node (ref "X4") (pin "3") (pinfunction "3_3") (pintype "passive"))
      (node (ref "X4") (pin "SH1") (pinfunction "PE1_SH1") (pintype "power_in"))
      (node (ref "X4") (pin "SH2") (pinfunction "PE2_SH2") (pintype "power_in"))
      (node (ref "X4") (pin "SH3") (pinfunction "PE3_SH3") (pintype "power_in"))
      (node (ref "X5") (pin "1") (pinfunction "1_1") (pintype "passive"))
    )
    (net (code "61") (name "IRQ") (class "Default")
      (node (ref "IC17") (pin "14") (pinfunction "GS_14") (pintype "output"))
      (node (ref "IC4") (pin "4") (pinfunction "IRQB_4") (pintype "input"))
      (node (ref "LED3") (pin "K") (pinfunction "C_K") (pintype "passive"))
    )
    (net (code "62") (name "IRQ0") (class "Default")
      (node (ref "IC17") (pin "4") (pinfunction "7_4") (pintype "input"))
      (node (ref "IC19") (pin "26") (pinfunction "IRQ_26") (pintype "output"))
      (node (ref "RN1") (pin "2") (pinfunction "2_2") (pintype "passive"))
    )
    (net (code "63") (name "IRQ1") (class "Default")
      (node (ref "IC16") (pin "21") (pinfunction "~{IRQB}_21") (pintype "output"))
      (node (ref "IC17") (pin "3") (pinfunction "6_3") (pintype "input"))
      (node (ref "RN1") (pin "3") (pinfunction "3_3") (pintype "passive"))
    )
    (net (code "64") (name "IRQ2") (class "Default")
      (node (ref "IC17") (pin "2") (pinfunction "5_2") (pintype "input"))
      (node (ref "RN1") (pin "4") (pinfunction "4_4") (pintype "passive"))
      (node (ref "X1") (pin "B25") (pinfunction "P_B25") (pintype "passive"))
      (node (ref "X2") (pin "B25") (pinfunction "P_B25") (pintype "passive"))
      (node (ref "X3") (pin "B25") (pinfunction "P_B25") (pintype "passive"))
    )
    (net (code "65") (name "IRQ3") (class "Default")
      (node (ref "IC17") (pin "1") (pinfunction "4_1") (pintype "input"))
      (node (ref "RN1") (pin "5") (pinfunction "5_5") (pintype "passive"))
      (node (ref "X1") (pin "B24") (pinfunction "P_B24") (pintype "passive"))
      (node (ref "X2") (pin "B24") (pinfunction "P_B24") (pintype "passive"))
      (node (ref "X3") (pin "B24") (pinfunction "P_B24") (pintype "passive"))
    )
    (net (code "66") (name "IRQ4") (class "Default")
      (node (ref "IC17") (pin "13") (pinfunction "3_13") (pintype "input"))
      (node (ref "RN1") (pin "6") (pinfunction "6_6") (pintype "passive"))
      (node (ref "X1") (pin "B23") (pinfunction "P_B23") (pintype "passive"))
      (node (ref "X2") (pin "B23") (pinfunction "P_B23") (pintype "passive"))
      (node (ref "X3") (pin "B23") (pinfunction "P_B23") (pintype "passive"))
    )
    (net (code "67") (name "IRQ5") (class "Default")
      (node (ref "IC17") (pin "12") (pinfunction "2_12") (pintype "input"))
      (node (ref "RN1") (pin "7") (pinfunction "7_7") (pintype "passive"))
      (node (ref "X1") (pin "B22") (pinfunction "P_B22") (pintype "passive"))
      (node (ref "X2") (pin "B22") (pinfunction "P_B22") (pintype "passive"))
      (node (ref "X3") (pin "B22") (pinfunction "P_B22") (pintype "passive"))
    )
    (net (code "68") (name "IRQ6") (class "Default")
      (node (ref "IC17") (pin "11") (pinfunction "1_11") (pintype "input"))
      (node (ref "RN1") (pin "8") (pinfunction "8_8") (pintype "passive"))
      (node (ref "X1") (pin "B21") (pinfunction "P_B21") (pintype "passive"))
      (node (ref "X2") (pin "B21") (pinfunction "P_B21") (pintype "passive"))
      (node (ref "X3") (pin "B21") (pinfunction "P_B21") (pintype "passive"))
    )
    (net (code "69") (name "IRQ7") (class "Default")
      (node (ref "IC17") (pin "10") (pinfunction "0_10") (pintype "input"))
      (node (ref "RN1") (pin "9") (pinfunction "9_9") (pintype "passive"))
      (node (ref "S1") (pin "3") (pinfunction "P_3") (pintype "passive"))
      (node (ref "S1") (pin "4") (pinfunction "P1_4") (pintype "passive"))
    )
    (net (code "70") (name "MISO") (class "Default")
      (node (ref "IC14") (pin "2") (pinfunction "(PCINT9/OC1A/DO/MISO)PB1_2") (pintype "bidirectional"))
      (node (ref "J2") (pin "1") (pinfunction "1_1") (pintype "passive"))
    )
    (net (code "71") (name "MLB") (class "Default")
      (node (ref "IC4") (pin "5") (pinfunction "MLB_5") (pintype "output"))
    )
    (net (code "72") (name "MOSI") (class "Default")
      (node (ref "IC14") (pin "1") (pinfunction "(PCINT8/~{OC1A}/SDA/DI/MOSI)PB0_1") (pintype "bidirectional"))
      (node (ref "J2") (pin "4") (pinfunction "4_4") (pintype "passive"))
    )
    (net (code "73") (name "NMI") (class "Default")
      (node (ref "IC18") (pin "21") (pinfunction "~{IRQB}_21") (pintype "output"))
      (node (ref "IC4") (pin "6") (pinfunction "NMIB_6") (pintype "input"))
      (node (ref "R8") (pin "2") (pinfunction "2_2") (pintype "passive"))
      (node (ref "S2") (pin "3") (pinfunction "P_3") (pintype "passive"))
      (node (ref "S2") (pin "4") (pinfunction "P1_4") (pintype "passive"))
      (node (ref "X1") (pin "B19") (pinfunction "P_B19") (pintype "passive"))
      (node (ref "X2") (pin "B19") (pinfunction "P_B19") (pintype "passive"))
      (node (ref "X3") (pin "B19") (pinfunction "P_B19") (pintype "passive"))
    )
    (net (code "74") (name "Net-(C34-Pad2)") (class "Default")
      (node (ref "C34") (pin "2") (pinfunction "2_2") (pintype "passive"))
      (node (ref "C36") (pin "1") (pinfunction "1_1") (pintype "passive"))
      (node (ref "R22") (pin "2") (pinfunction "2_2") (pintype "passive"))
    )
    (net (code "75") (name "Net-(C35-Pad2)") (class "Default")
      (node (ref "C35") (pin "2") (pinfunction "2_2") (pintype "passive"))
      (node (ref "C37") (pin "1") (pinfunction "1_1") (pintype "passive"))
      (node (ref "R23") (pin "2") (pinfunction "2_2") (pintype "passive"))
    )
    (net (code "76") (name "Net-(IC2A-CLR)") (class "Default")
      (node (ref "IC2") (pin "1") (pinfunction "CLR_1") (pintype "input"))
      (node (ref "IC2") (pin "4") (pinfunction "PRE_4") (pintype "input"))
      (node (ref "R3") (pin "2") (pinfunction "2_2") (pintype "passive"))
    )
    (net (code "77") (name "Net-(IC2A-D)") (class "Default")
      (node (ref "IC2") (pin "2") (pinfunction "D_2") (pintype "input"))
      (node (ref "IC2") (pin "6") (pinfunction "~{Q}_6") (pintype "output"))
    )
    (net (code "78") (name "Net-(IC2B-CLR)") (class "Default")
      (node (ref "IC2") (pin "10") (pinfunction "PRE_10") (pintype "input"))
      (node (ref "IC2") (pin "13") (pinfunction "CLR_13") (pintype "input"))
      (node (ref "R4") (pin "2") (pinfunction "2_2") (pintype "passive"))
    )
    (net (code "79") (name "Net-(IC2B-D)") (class "Default")
      (node (ref "IC2") (pin "12") (pinfunction "D_12") (pintype "input"))
      (node (ref "IC2") (pin "8") (pinfunction "~{Q}_8") (pintype "output"))
    )
    (net (code "80") (name "Net-(IC3A-CLR)") (class "Default")
      (node (ref "IC3") (pin "1") (pinfunction "CLR_1") (pintype "input"))
      (node (ref "IC3") (pin "4") (pinfunction "PRE_4") (pintype "input"))
      (node (ref "R5") (pin "2") (pinfunction "2_2") (pintype "passive"))
    )
    (net (code "81") (name "Net-(IC3A-D)") (class "Default")
      (node (ref "IC3") (pin "2") (pinfunction "D_2") (pintype "input"))
      (node (ref "IC3") (pin "6") (pinfunction "~{Q}_6") (pintype "output"))
    )
    (net (code "82") (name "Net-(IC3B-CLR)") (class "Default")
      (node (ref "IC3") (pin "10") (pinfunction "PRE_10") (pintype "input"))
      (node (ref "IC3") (pin "13") (pinfunction "CLR_13") (pintype "input"))
      (node (ref "R6") (pin "2") (pinfunction "2_2") (pintype "passive"))
    )
    (net (code "83") (name "Net-(IC3B-D)") (class "Default")
      (node (ref "IC3") (pin "12") (pinfunction "D_12") (pintype "input"))
      (node (ref "IC3") (pin "8") (pinfunction "~{Q}_8") (pintype "output"))
    )
    (net (code "84") (name "Net-(IC10A-O)") (class "Default")
      (node (ref "IC10") (pin "10") (pinfunction "I1_10") (pintype "input"))
      (node (ref "IC10") (pin "3") (pinfunction "O_3") (pintype "output"))
    )
    (net (code "85") (name "Net-(IC19-XTL1)") (class "Default")
      (node (ref "C29") (pin "2") (pinfunction "2_2") (pintype "passive"))
      (node (ref "IC19") (pin "6") (pinfunction "XTL1_6") (pintype "input"))
      (node (ref "Q1") (pin "1") (pinfunction "1_1") (pintype "passive"))
    )
    (net (code "86") (name "Net-(IC19-XTL2)") (class "Default")
      (node (ref "IC19") (pin "7") (pinfunction "XTL2_7") (pintype "output"))
      (node (ref "Q1") (pin "2") (pinfunction "2_2") (pintype "passive"))
    )
    (net (code "87") (name "Net-(L1-Pad2)") (class "Default")
      (node (ref "L1") (pin "2") (pinfunction "2_2") (pintype "passive"))
      (node (ref "R18") (pin "2") (pinfunction "2_2") (pintype "passive"))
      (node (ref "R19") (pin "2") (pinfunction "2_2") (pintype "passive"))
    )
    (net (code "88") (name "Net-(LED1-PadA)") (class "Default")
      (node (ref "LED1") (pin "A") (pinfunction "A_A") (pintype "passive"))
      (node (ref "R1") (pin "1") (pinfunction "1_1") (pintype "passive"))
    )
    (net (code "89") (name "Net-(LED2-PadA)") (class "Default")
      (node (ref "LED2") (pin "A") (pinfunction "A_A") (pintype "passive"))
      (node (ref "R2") (pin "1") (pinfunction "1_1") (pintype "passive"))
    )
    (net (code "90") (name "Net-(LED3-PadA)") (class "Default")
      (node (ref "LED3") (pin "A") (pinfunction "A_A") (pintype "passive"))
      (node (ref "R10") (pin "1") (pinfunction "1_1") (pintype "passive"))
    )
    (net (code "91") (name "Net-(LED4-PadA)") (class "Default")
      (node (ref "LED4") (pin "A") (pinfunction "A_A") (pintype "passive"))
      (node (ref "R11") (pin "1") (pinfunction "1_1") (pintype "passive"))
    )
    (net (code "92") (name "Net-(LED5-PadA)") (class "Default")
      (node (ref "LED5") (pin "A") (pinfunction "A_A") (pintype "passive"))
      (node (ref "R12") (pin "1") (pinfunction "1_1") (pintype "passive"))
    )
    (net (code "93") (name "Net-(LED6-PadA)") (class "Default")
      (node (ref "LED6") (pin "A") (pinfunction "A_A") (pintype "passive"))
      (node (ref "R14") (pin "2") (pinfunction "2_2") (pintype "passive"))
    )
    (net (code "94") (name "Net-(LED7-PadA)") (class "Default")
      (node (ref "LED7") (pin "A") (pinfunction "A_A") (pintype "passive"))
      (node (ref "R15") (pin "2") (pinfunction "2_2") (pintype "passive"))
    )
    (net (code "95") (name "Net-(X1AG-P)") (class "Default")
      (node (ref "X1") (pin "B10") (pinfunction "P_B10") (pintype "passive"))
      (node (ref "X2") (pin "B10") (pinfunction "P_B10") (pintype "passive"))
      (node (ref "X3") (pin "B10") (pinfunction "P_B10") (pintype "passive"))
    )
    (net (code "96") (name "Net-(X1AJ-P)") (class "Default")
      (node (ref "X1") (pin "B13") (pinfunction "P_B13") (pintype "passive"))
      (node (ref "X2") (pin "B13") (pinfunction "P_B13") (pintype "passive"))
      (node (ref "X3") (pin "B13") (pinfunction "P_B13") (pintype "passive"))
    )
    (net (code "97") (name "Net-(X1AK-P)") (class "Default")
      (node (ref "X1") (pin "B14") (pinfunction "P_B14") (pintype "passive"))
      (node (ref "X2") (pin "B14") (pinfunction "P_B14") (pintype "passive"))
      (node (ref "X3") (pin "B14") (pinfunction "P_B14") (pintype "passive"))
    )
    (net (code "98") (name "Net-(X1AL-P)") (class "Default")
      (node (ref "X1") (pin "B15") (pinfunction "P_B15") (pintype "passive"))
      (node (ref "X2") (pin "B15") (pinfunction "P_B15") (pintype "passive"))
      (node (ref "X3") (pin "B15") (pinfunction "P_B15") (pintype "passive"))
    )
    (net (code "99") (name "Net-(X1AM-P)") (class "Default")
      (node (ref "X1") (pin "B16") (pinfunction "P_B16") (pintype "passive"))
      (node (ref "X2") (pin "B16") (pinfunction "P_B16") (pintype "passive"))
      (node (ref "X3") (pin "B16") (pinfunction "P_B16") (pintype "passive"))
    )
    (net (code "100") (name "Net-(X1AN-P)") (class "Default")
      (node (ref "X1") (pin "B17") (pinfunction "P_B17") (pintype "passive"))
      (node (ref "X2") (pin "B17") (pinfunction "P_B17") (pintype "passive"))
      (node (ref "X3") (pin "B17") (pinfunction "P_B17") (pintype "passive"))
    )
    (net (code "101") (name "Net-(X1AX-P)") (class "Default")
      (node (ref "X1") (pin "B26") (pinfunction "P_B26") (pintype "passive"))
      (node (ref "X2") (pin "B26") (pinfunction "P_B26") (pintype "passive"))
      (node (ref "X3") (pin "B26") (pinfunction "P_B26") (pintype "passive"))
    )
    (net (code "102") (name "Net-(X1AY-P)") (class "Default")
      (node (ref "X1") (pin "B27") (pinfunction "P_B27") (pintype "passive"))
      (node (ref "X2") (pin "B27") (pinfunction "P_B27") (pintype "passive"))
      (node (ref "X3") (pin "B27") (pinfunction "P_B27") (pintype "passive"))
    )
    (net (code "103") (name "Net-(X1BG-P)") (class "Default")
      (node (ref "X1") (pin "B6") (pinfunction "P_B6") (pintype "passive"))
      (node (ref "X2") (pin "B6") (pinfunction "P_B6") (pintype "passive"))
      (node (ref "X3") (pin "B6") (pinfunction "P_B6") (pintype "passive"))
    )
    (net (code "104") (name "Net-(X1BH-P)") (class "Default")
      (node (ref "X1") (pin "B7") (pinfunction "P_B7") (pintype "passive"))
      (node (ref "X2") (pin "B7") (pinfunction "P_B7") (pintype "passive"))
      (node (ref "X3") (pin "B7") (pinfunction "P_B7") (pintype "passive"))
    )
    (net (code "105") (name "Net-(X1BI-P)") (class "Default")
      (node (ref "X1") (pin "B8") (pinfunction "P_B8") (pintype "passive"))
      (node (ref "X2") (pin "B8") (pinfunction "P_B8") (pintype "passive"))
      (node (ref "X3") (pin "B8") (pinfunction "P_B8") (pintype "passive"))
    )
    (net (code "106") (name "Net-(X1BJ-P)") (class "Default")
      (node (ref "X1") (pin "B9") (pinfunction "P_B9") (pintype "passive"))
      (node (ref "X2") (pin "B9") (pinfunction "P_B9") (pintype "passive"))
      (node (ref "X3") (pin "B9") (pinfunction "P_B9") (pintype "passive"))
    )
    (net (code "107") (name "OUTL") (class "Default")
      (node (ref "C32") (pin "2") (pinfunction "2_2") (pintype "passive"))
      (node (ref "IC20") (pin "5") (pinfunction "OUTL_5") (pintype "bidirectional"))
      (node (ref "R20") (pin "2") (pinfunction "2_2") (pintype "passive"))
      (node (ref "R22") (pin "1") (pinfunction "1_1") (pintype "passive"))
    )
    (net (code "108") (name "OUTR") (class "Default")
      (node (ref "C33") (pin "2") (pinfunction "2_2") (pintype "passive"))
      (node (ref "IC20") (pin "4") (pinfunction "OUTR_4") (pintype "bidirectional"))
      (node (ref "R21") (pin "2") (pinfunction "2_2") (pintype "passive"))
      (node (ref "R23") (pin "1") (pinfunction "1_1") (pintype "passive"))
    )
    (net (code "109") (name "PA0") (class "Default")
      (node (ref "IC16") (pin "2") (pinfunction "PA0_2") (pintype "bidirectional"))
      (node (ref "JP8") (pin "3") (pinfunction "3_3") (pintype "passive"))
    )
    (net (code "110") (name "PA1") (class "Default")
      (node (ref "IC16") (pin "3") (pinfunction "PA1_3") (pintype "bidirectional"))
      (node (ref "JP8") (pin "5") (pinfunction "5_5") (pintype "passive"))
    )
    (net (code "111") (name "PA2") (class "Default")
      (node (ref "IC16") (pin "4") (pinfunction "PA2_4") (pintype "bidirectional"))
      (node (ref "JP8") (pin "7") (pinfunction "7_7") (pintype "passive"))
    )
    (net (code "112") (name "PA3") (class "Default")
      (node (ref "IC16") (pin "5") (pinfunction "PA3_5") (pintype "bidirectional"))
      (node (ref "JP8") (pin "9") (pinfunction "9_9") (pintype "passive"))
    )
    (net (code "113") (name "PA4") (class "Default")
      (node (ref "IC16") (pin "6") (pinfunction "PA4_6") (pintype "bidirectional"))
      (node (ref "JP8") (pin "11") (pinfunction "11_11") (pintype "passive"))
    )
    (net (code "114") (name "PA5") (class "Default")
      (node (ref "IC16") (pin "7") (pinfunction "PA5_7") (pintype "bidirectional"))
      (node (ref "JP8") (pin "13") (pinfunction "13_13") (pintype "passive"))
    )
    (net (code "115") (name "PA6") (class "Default")
      (node (ref "IC16") (pin "8") (pinfunction "PA6_8") (pintype "bidirectional"))
      (node (ref "JP8") (pin "15") (pinfunction "15_15") (pintype "passive"))
    )
    (net (code "116") (name "PA7") (class "Default")
      (node (ref "IC16") (pin "9") (pinfunction "PA7_9") (pintype "bidirectional"))
      (node (ref "JP8") (pin "17") (pinfunction "17_17") (pintype "passive"))
    )
    (net (code "117") (name "PB0") (class "Default")
      (node (ref "IC16") (pin "10") (pinfunction "PB0_10") (pintype "bidirectional"))
      (node (ref "JP8") (pin "4") (pinfunction "4_4") (pintype "passive"))
    )
    (net (code "118") (name "PB1") (class "Default")
      (node (ref "IC16") (pin "11") (pinfunction "PB1_11") (pintype "bidirectional"))
      (node (ref "JP8") (pin "6") (pinfunction "6_6") (pintype "passive"))
    )
    (net (code "119") (name "PB2") (class "Default")
      (node (ref "IC16") (pin "12") (pinfunction "PB2_12") (pintype "bidirectional"))
      (node (ref "JP8") (pin "8") (pinfunction "8_8") (pintype "passive"))
    )
    (net (code "120") (name "PB3") (class "Default")
      (node (ref "IC16") (pin "13") (pinfunction "PB3_13") (pintype "bidirectional"))
      (node (ref "JP8") (pin "10") (pinfunction "10_10") (pintype "passive"))
    )
    (net (code "121") (name "PB4") (class "Default")
      (node (ref "IC16") (pin "14") (pinfunction "PB4_14") (pintype "bidirectional"))
      (node (ref "JP8") (pin "12") (pinfunction "12_12") (pintype "passive"))
    )
    (net (code "122") (name "PB5") (class "Default")
      (node (ref "IC16") (pin "15") (pinfunction "PB5_15") (pintype "bidirectional"))
      (node (ref "JP8") (pin "14") (pinfunction "14_14") (pintype "passive"))
    )
    (net (code "123") (name "PB6") (class "Default")
      (node (ref "IC16") (pin "16") (pinfunction "PB6_16") (pintype "bidirectional"))
      (node (ref "JP8") (pin "16") (pinfunction "16_16") (pintype "passive"))
    )
    (net (code "124") (name "PB7") (class "Default")
      (node (ref "IC16") (pin "17") (pinfunction "PB7_17") (pintype "bidirectional"))
      (node (ref "JP8") (pin "18") (pinfunction "18_18") (pintype "passive"))
    )
    (net (code "125") (name "PHI2") (class "Default")
      (node (ref "IC10") (pin "13") (pinfunction "I1_13") (pintype "input"))
      (node (ref "IC10") (pin "9") (pinfunction "I0_9") (pintype "input"))
      (node (ref "IC16") (pin "25") (pinfunction "PHI2_25") (pintype "input"))
      (node (ref "IC18") (pin "25") (pinfunction "PHI2_25") (pintype "input"))
      (node (ref "IC19") (pin "27") (pinfunction "PHI2_27") (pintype "input"))
      (node (ref "IC4") (pin "39") (pinfunction "PHI2_39") (pintype "output"))
      (node (ref "X1") (pin "B20") (pinfunction "P_B20") (pintype "passive"))
      (node (ref "X2") (pin "B20") (pinfunction "P_B20") (pintype "passive"))
      (node (ref "X3") (pin "B20") (pinfunction "P_B20") (pintype "passive"))
    )
    (net (code "126") (name "PS2_CLK") (class "Default")
      (node (ref "IC14") (pin "4") (pinfunction "(PCINT11/OC1B)PB3_4") (pintype "bidirectional"))
      (node (ref "X4") (pin "6") (pinfunction "6_6") (pintype "passive"))
    )
    (net (code "127") (name "PS2_DATA") (class "Default")
      (node (ref "IC14") (pin "7") (pinfunction "PB4(ADC7/XTAL1/PCINT12)_7") (pintype "bidirectional"))
      (node (ref "X4") (pin "1") (pinfunction "1_1") (pintype "passive"))
    )
    (net (code "128") (name "RDY") (class "Default")
      (node (ref "IC4") (pin "2") (pinfunction "RDY_2") (pintype "bidirectional"))
      (node (ref "R7") (pin "2") (pinfunction "2_2") (pintype "passive"))
    )
    (net (code "129") (name "RESET") (class "Default")
      (node (ref "IC16") (pin "34") (pinfunction "~{RESB}_34") (pintype "input"))
      (node (ref "IC18") (pin "34") (pinfunction "~{RESB}_34") (pintype "input"))
      (node (ref "IC19") (pin "4") (pinfunction "RES_4") (pintype "input"))
      (node (ref "IC4") (pin "40") (pinfunction "RESB_40") (pintype "input"))
      (node (ref "IC8") (pin "1") (pinfunction "~{RESET}_1") (pintype "bidirectional"))
      (node (ref "LED5") (pin "K") (pinfunction "C_K") (pintype "passive"))
      (node (ref "R13") (pin "2") (pinfunction "2_2") (pintype "passive"))
      (node (ref "S3") (pin "3") (pinfunction "P_3") (pintype "passive"))
      (node (ref "S3") (pin "4") (pinfunction "P1_4") (pintype "passive"))
      (node (ref "SJ1") (pin "1") (pinfunction "1_1") (pintype "passive"))
      (node (ref "X1") (pin "B2") (pinfunction "P_B2") (pintype "passive"))
      (node (ref "X2") (pin "B2") (pinfunction "P_B2") (pintype "passive"))
      (node (ref "X3") (pin "B2") (pinfunction "P_B2") (pintype "passive"))
    )
    (net (code "130") (name "RTS") (class "Default")
      (node (ref "IC19") (pin "8") (pinfunction "RTS_8") (pintype "output"))
      (node (ref "JP12") (pin "1") (pinfunction "1_1") (pintype "passive"))
    )
    (net (code "131") (name "RX") (class "Default")
      (node (ref "IC19") (pin "10") (pinfunction "TXD_10") (pintype "output"))
      (node (ref "JP11") (pin "2") (pinfunction "2_2") (pintype "passive"))
      (node (ref "X1") (pin "B4") (pinfunction "P_B4") (pintype "passive"))
      (node (ref "X2") (pin "B4") (pinfunction "P_B4") (pintype "passive"))
      (node (ref "X3") (pin "B4") (pinfunction "P_B4") (pintype "passive"))
    )
    (net (code "132") (name "R{slash}~{W}") (class "Default")
      (node (ref "IC10") (pin "1") (pinfunction "I0_1") (pintype "input"))
      (node (ref "IC10") (pin "12") (pinfunction "I0_12") (pintype "input"))
      (node (ref "IC10") (pin "2") (pinfunction "I1_2") (pintype "input"))
      (node (ref "IC16") (pin "22") (pinfunction "R~{WB}_22") (pintype "input"))
      (node (ref "IC18") (pin "22") (pinfunction "R~{WB}_22") (pintype "input"))
      (node (ref "IC19") (pin "28") (pinfunction "R/W_28") (pintype "input"))
      (node (ref "IC4") (pin "34") (pinfunction "R/WB_34") (pintype "output"))
      (node (ref "X1") (pin "A1") (pinfunction "P_A1") (pintype "passive"))
      (node (ref "X2") (pin "A1") (pinfunction "P_A1") (pintype "passive"))
      (node (ref "X3") (pin "A1") (pinfunction "P_A1") (pintype "passive"))
    )
    (net (code "133") (name "SAA_DACK") (class "Default")
      (node (ref "IC20") (pin "7") (pinfunction "DTACK_7") (pintype "bidirectional"))
      (node (ref "R18") (pin "1") (pinfunction "1_1") (pintype "passive"))
    )
    (net (code "134") (name "SAA_IREF") (class "Default")
      (node (ref "IC20") (pin "6") (pinfunction "IREF_6") (pintype "bidirectional"))
      (node (ref "R19") (pin "1") (pinfunction "1_1") (pintype "passive"))
    )
    (net (code "135") (name "SCK") (class "Default")
      (node (ref "IC14") (pin "3") (pinfunction "(PCINT10/~{OC1B}/SCL/SCK)PB2_3") (pintype "bidirectional"))
      (node (ref "J2") (pin "3") (pinfunction "3_3") (pintype "passive"))
    )
    (net (code "136") (name "SOUND_L") (class "Default")
      (node (ref "C36") (pin "2") (pinfunction "2_2") (pintype "passive"))
      (node (ref "X5") (pin "2") (pinfunction "2_2") (pintype "passive"))
    )
    (net (code "137") (name "SOUND_R") (class "Default")
      (node (ref "C37") (pin "2") (pinfunction "2_2") (pintype "passive"))
      (node (ref "X5") (pin "5") (pinfunction "5_5") (pintype "passive"))
    )
    (net (code "138") (name "SYNC") (class "Default")
      (node (ref "IC4") (pin "7") (pinfunction "SYNC_7") (pintype "output"))
    )
    (net (code "139") (name "TX") (class "Default")
      (node (ref "IC19") (pin "12") (pinfunction "RXD_12") (pintype "input"))
      (node (ref "JP11") (pin "3") (pinfunction "3_3") (pintype "passive"))
      (node (ref "X1") (pin "B5") (pinfunction "P_B5") (pintype "passive"))
      (node (ref "X2") (pin "B5") (pinfunction "P_B5") (pintype "passive"))
      (node (ref "X3") (pin "B5") (pinfunction "P_B5") (pintype "passive"))
    )
    (net (code "140") (name "VCC") (class "Default")
      (node (ref "J1") (pin "1") (pinfunction "1_1") (pintype "passive"))
      (node (ref "JP1") (pin "1") (pinfunction "1_1") (pintype "passive"))
    )
    (net (code "141") (name "VPB") (class "Default")
      (node (ref "IC4") (pin "1") (pinfunction "VPB_1") (pintype "output"))
    )
    (net (code "142") (name "unconnected-(IC4-NC-Pad35)") (class "Default")
      (node (ref "IC4") (pin "35") (pinfunction "NC_35") (pintype "no_connect"))
    )
    (net (code "143") (name "unconnected-(IC4-PHI1-Pad3)") (class "Default")
      (node (ref "IC4") (pin "3") (pinfunction "PHI1_3") (pintype "output"))
    )
    (net (code "144") (name "unconnected-(IC4-SOB-Pad38)") (class "Default")
      (node (ref "IC4") (pin "38") (pinfunction "SOB_38") (pintype "input"))
    )
    (net (code "145") (name "unconnected-(IC5-RDY{slash}~{BSY}-Pad1)") (class "Default")
      (node (ref "IC5") (pin "1") (pinfunction "RDY/~{BSY}_1") (pintype "output"))
    )
    (net (code "146") (name "unconnected-(IC11A-Y0-Pad4)") (class "Default")
      (node (ref "IC11") (pin "4") (pinfunction "Y0_4") (pintype "output"))
    )
    (net (code "147") (name "unconnected-(IC11A-Y1-Pad5)") (class "Default")
      (node (ref "IC11") (pin "5") (pinfunction "Y1_5") (pintype "output"))
    )
    (net (code "148") (name "unconnected-(IC11B-Y2-Pad10)") (class "Default")
      (node (ref "IC11") (pin "10") (pinfunction "Y2_10") (pintype "output"))
    )
    (net (code "149") (name "unconnected-(IC11B-Y3-Pad9)") (class "Default")
      (node (ref "IC11") (pin "9") (pinfunction "Y3_9") (pintype "output"))
    )
    (net (code "150") (name "unconnected-(IC17A-A0-Pad9)") (class "Default")
      (node (ref "IC17") (pin "9") (pinfunction "A0_9") (pintype "output"))
    )
    (net (code "151") (name "unconnected-(IC17A-A1-Pad7)") (class "Default")
      (node (ref "IC17") (pin "7") (pinfunction "A1_7") (pintype "output"))
    )
    (net (code "152") (name "unconnected-(IC17A-A2-Pad6)") (class "Default")
      (node (ref "IC17") (pin "6") (pinfunction "A2_6") (pintype "output"))
    )
    (net (code "153") (name "unconnected-(IC17A-EO-Pad15)") (class "Default")
      (node (ref "IC17") (pin "15") (pinfunction "EO_15") (pintype "output"))
    )
    (net (code "154") (name "unconnected-(IC18A-CA1-Pad40)") (class "Default")
      (node (ref "IC18") (pin "40") (pinfunction "CA1_40") (pintype "bidirectional"))
    )
    (net (code "155") (name "unconnected-(IC18A-CA2-Pad39)") (class "Default")
      (node (ref "IC18") (pin "39") (pinfunction "CA2_39") (pintype "bidirectional"))
    )
    (net (code "156") (name "unconnected-(IC18A-CB1-Pad18)") (class "Default")
      (node (ref "IC18") (pin "18") (pinfunction "CB1_18") (pintype "bidirectional"))
    )
    (net (code "157") (name "unconnected-(IC18A-CB2-Pad19)") (class "Default")
      (node (ref "IC18") (pin "19") (pinfunction "CB2_19") (pintype "bidirectional"))
    )
    (net (code "158") (name "unconnected-(IC19-DTR-Pad11)") (class "Default")
      (node (ref "IC19") (pin "11") (pinfunction "DTR_11") (pintype "output"))
    )
    (net (code "159") (name "unconnected-(IC19-RXC-Pad5)") (class "Default")
      (node (ref "IC19") (pin "5") (pinfunction "RXC_5") (pintype "bidirectional"))
    )
    (net (code "160") (name "unconnected-(IC21B-I0-Pad4)") (class "Default")
      (node (ref "IC21") (pin "4") (pinfunction "I0_4") (pintype "input"))
    )
    (net (code "161") (name "unconnected-(IC21B-I1-Pad5)") (class "Default")
      (node (ref "IC21") (pin "5") (pinfunction "I1_5") (pintype "input"))
    )
    (net (code "162") (name "unconnected-(IC21B-O-Pad6)") (class "Default")
      (node (ref "IC21") (pin "6") (pinfunction "O_6") (pintype "output"))
    )
    (net (code "163") (name "unconnected-(IC21C-I0-Pad9)") (class "Default")
      (node (ref "IC21") (pin "9") (pinfunction "I0_9") (pintype "input"))
    )
    (net (code "164") (name "unconnected-(IC21C-I1-Pad10)") (class "Default")
      (node (ref "IC21") (pin "10") (pinfunction "I1_10") (pintype "input"))
    )
    (net (code "165") (name "unconnected-(IC21C-O-Pad8)") (class "Default")
      (node (ref "IC21") (pin "8") (pinfunction "O_8") (pintype "output"))
    )
    (net (code "166") (name "unconnected-(IC21D-I0-Pad12)") (class "Default")
      (node (ref "IC21") (pin "12") (pinfunction "I0_12") (pintype "input"))
    )
    (net (code "167") (name "unconnected-(IC21D-I1-Pad13)") (class "Default")
      (node (ref "IC21") (pin "13") (pinfunction "I1_13") (pintype "input"))
    )
    (net (code "168") (name "unconnected-(IC21D-O-Pad11)") (class "Default")
      (node (ref "IC21") (pin "11") (pinfunction "O_11") (pintype "output"))
    )
    (net (code "169") (name "unconnected-(J3-Pad5)") (class "Default")
      (node (ref "J3") (pin "5") (pinfunction "5_5") (pintype "passive"))
    )
    (net (code "170") (name "unconnected-(J3-Pad9)") (class "Default")
      (node (ref "J3") (pin "9") (pinfunction "9_9") (pintype "passive"))
    )
    (net (code "171") (name "unconnected-(JP11-Pad5)") (class "Default")
      (node (ref "JP11") (pin "5") (pinfunction "5_5") (pintype "passive"))
    )
    (net (code "172") (name "unconnected-(RN2-Pad2)") (class "Default")
      (node (ref "RN2") (pin "2") (pinfunction "2_2") (pintype "passive"))
    )
    (net (code "173") (name "unconnected-(RN2-Pad3)") (class "Default")
      (node (ref "RN2") (pin "3") (pinfunction "3_3") (pintype "passive"))
    )
    (net (code "174") (name "unconnected-(X4-Pad2)") (class "Default")
      (node (ref "X4") (pin "2") (pinfunction "2_2") (pintype "passive"))
    )
    (net (code "175") (name "unconnected-(X4-Pad8)") (class "Default")
      (node (ref "X4") (pin "8") (pinfunction "8_8") (pintype "passive"))
    )
    (net (code "176") (name "unconnected-(X5-Pad3)") (class "Default")
      (node (ref "X5") (pin "3") (pinfunction "3_3") (pintype "passive"))
    )
    (net (code "177") (name "unconnected-(X5-Pad4)") (class "Default")
      (node (ref "X5") (pin "4") (pinfunction "4_4") (pintype "passive"))
    )
    (net (code "178") (name "~{A7}") (class "Default")
      (node (ref "IC10") (pin "6") (pinfunction "O_6") (pintype "output"))
      (node (ref "IC18") (pin "24") (pinfunction "CS1_24") (pintype "input"))
    )
    (net (code "179") (name "~{AA_CS_WR}") (class "Default")
      (node (ref "IC20") (pin "1") (pinfunction "~{WR}_1") (pintype "bidirectional"))
      (node (ref "IC20") (pin "2") (pinfunction "~{CS}_2") (pintype "bidirectional"))
      (node (ref "IC21") (pin "3") (pinfunction "O_3") (pintype "output"))
    )
    (net (code "180") (name "~{AA_CS}") (class "Default")
      (node (ref "IC21") (pin "1") (pinfunction "I0_1") (pintype "input"))
      (node (ref "IC9") (pin "5") (pinfunction "Y1_5") (pintype "output"))
      (node (ref "JP6") (pin "10") (pinfunction "10_10") (pintype "passive"))
    )
    (net (code "181") (name "~{ACIA_CS}") (class "Default")
      (node (ref "IC19") (pin "3") (pinfunction "CS1_3") (pintype "input"))
      (node (ref "IC9") (pin "6") (pinfunction "Y2_6") (pintype "output"))
      (node (ref "JP6") (pin "8") (pinfunction "8_8") (pintype "passive"))
    )
    (net (code "182") (name "~{C-F}") (class "Default")
      (node (ref "IC11") (pin "15") (pinfunction "G_15") (pintype "input"))
      (node (ref "IC11") (pin "7") (pinfunction "Y3_7") (pintype "output"))
      (node (ref "IC12") (pin "1") (pinfunction "I0_1") (pintype "input"))
      (node (ref "IC12") (pin "2") (pinfunction "I1_2") (pintype "input"))
    )
    (net (code "183") (name "~{DEV0_CS}") (class "Default")
      (node (ref "IC9") (pin "11") (pinfunction "Y1_11") (pintype "output"))
      (node (ref "X1") (pin "A14") (pinfunction "P_A14") (pintype "passive"))
      (node (ref "X2") (pin "A14") (pinfunction "P_A14") (pintype "passive"))
      (node (ref "X3") (pin "A14") (pinfunction "P_A14") (pintype "passive"))
    )
    (net (code "184") (name "~{DEV1_CS}") (class "Default")
      (node (ref "IC9") (pin "10") (pinfunction "Y2_10") (pintype "output"))
      (node (ref "X1") (pin "A13") (pinfunction "P_A13") (pintype "passive"))
      (node (ref "X2") (pin "A13") (pinfunction "P_A13") (pintype "passive"))
      (node (ref "X3") (pin "A13") (pinfunction "P_A13") (pintype "passive"))
    )
    (net (code "185") (name "~{DEV2_CS}") (class "Default")
      (node (ref "IC9") (pin "9") (pinfunction "Y3_9") (pintype "output"))
      (node (ref "X1") (pin "A12") (pinfunction "P_A12") (pintype "passive"))
      (node (ref "X2") (pin "A12") (pinfunction "P_A12") (pintype "passive"))
      (node (ref "X3") (pin "A12") (pinfunction "P_A12") (pintype "passive"))
    )
    (net (code "186") (name "~{D_CS}") (class "Default")
      (node (ref "IC11") (pin "11") (pinfunction "Y1_11") (pintype "output"))
      (node (ref "X1") (pin "B28") (pinfunction "P_B28") (pintype "passive"))
      (node (ref "X2") (pin "B28") (pinfunction "P_B28") (pintype "passive"))
      (node (ref "X3") (pin "B28") (pinfunction "P_B28") (pintype "passive"))
    )
    (net (code "187") (name "~{E-F}") (class "Default")
      (node (ref "IC12") (pin "10") (pinfunction "I1_10") (pintype "input"))
      (node (ref "IC12") (pin "6") (pinfunction "O_6") (pintype "output"))
      (node (ref "IC12") (pin "9") (pinfunction "I0_9") (pintype "input"))
    )
    (net (code "188") (name "~{EXROM}") (class "Default")
      (node (ref "IC12") (pin "13") (pinfunction "I1_13") (pintype "input"))
      (node (ref "R16") (pin "1") (pinfunction "1_1") (pintype "passive"))
      (node (ref "X1") (pin "A15") (pinfunction "P_A15") (pintype "passive"))
      (node (ref "X2") (pin "A15") (pinfunction "P_A15") (pintype "passive"))
      (node (ref "X3") (pin "A15") (pinfunction "P_A15") (pintype "passive"))
    )
    (net (code "189") (name "~{HRAM_CS}") (class "Default")
      (node (ref "IC11") (pin "6") (pinfunction "Y2_6") (pintype "output"))
      (node (ref "IC7") (pin "20") (pinfunction "~{CS}_20") (pintype "input"))
      (node (ref "JP6") (pin "6") (pinfunction "6_6") (pintype "passive"))
    )
    (net (code "190") (name "~{IO_CS}") (class "Default")
      (node (ref "IC11") (pin "12") (pinfunction "Y0_12") (pintype "output"))
      (node (ref "IC9") (pin "1") (pinfunction "G_1") (pintype "input"))
      (node (ref "JP6") (pin "5") (pinfunction "5_5") (pintype "passive"))
      (node (ref "LED4") (pin "K") (pinfunction "C_K") (pintype "passive"))
      (node (ref "X1") (pin "A10") (pinfunction "P_A10") (pintype "passive"))
      (node (ref "X2") (pin "A10") (pinfunction "P_A10") (pintype "passive"))
      (node (ref "X3") (pin "A10") (pinfunction "P_A10") (pintype "passive"))
    )
    (net (code "191") (name "~{MEMR}") (class "Default")
      (node (ref "IC10") (pin "11") (pinfunction "O_11") (pintype "output"))
      (node (ref "IC5") (pin "22") (pinfunction "~{OE}_22") (pintype "input"))
      (node (ref "IC6") (pin "22") (pinfunction "~{OE}_22") (pintype "input"))
      (node (ref "IC7") (pin "22") (pinfunction "~{OE}_22") (pintype "input"))
      (node (ref "JP6") (pin "3") (pinfunction "3_3") (pintype "passive"))
      (node (ref "LED6") (pin "K") (pinfunction "C_K") (pintype "passive"))
      (node (ref "X1") (pin "B12") (pinfunction "P_B12") (pintype "passive"))
      (node (ref "X2") (pin "B12") (pinfunction "P_B12") (pintype "passive"))
      (node (ref "X3") (pin "B12") (pinfunction "P_B12") (pintype "passive"))
    )
    (net (code "192") (name "~{MEMW}") (class "Default")
      (node (ref "IC10") (pin "8") (pinfunction "O_8") (pintype "output"))
      (node (ref "IC21") (pin "2") (pinfunction "I1_2") (pintype "input"))
      (node (ref "IC6") (pin "27") (pinfunction "~{WE}_27") (pintype "input"))
      (node (ref "IC7") (pin "27") (pinfunction "~{WE}_27") (pintype "input"))
      (node (ref "JP6") (pin "2") (pinfunction "2_2") (pintype "passive"))
      (node (ref "LED7") (pin "K") (pinfunction "C_K") (pintype "passive"))
      (node (ref "X1") (pin "B11") (pinfunction "P_B11") (pintype "passive"))
      (node (ref "X2") (pin "B11") (pinfunction "P_B11") (pintype "passive"))
      (node (ref "X3") (pin "B11") (pinfunction "P_B11") (pintype "passive"))
    )
    (net (code "193") (name "~{OTHER_CS}") (class "Default")
      (node (ref "IC9") (pin "15") (pinfunction "G_15") (pintype "input"))
      (node (ref "IC9") (pin "7") (pinfunction "Y3_7") (pintype "output"))
    )
    (net (code "194") (name "~{RAM_CS}") (class "Default")
      (node (ref "JP6") (pin "7") (pinfunction "7_7") (pintype "passive"))
    )
    (net (code "195") (name "~{ROM_CS}") (class "Default")
      (node (ref "IC12") (pin "11") (pinfunction "O_11") (pintype "output"))
      (node (ref "IC5") (pin "20") (pinfunction "~{CE}_20") (pintype "input"))
      (node (ref "JP6") (pin "4") (pinfunction "4_4") (pintype "passive"))
    )
    (net (code "196") (name "~{SPI_CS}") (class "Default")
      (node (ref "IC9") (pin "4") (pinfunction "Y0_4") (pintype "output"))
      (node (ref "JP6") (pin "11") (pinfunction "11_11") (pintype "passive"))
    )
    (net (code "197") (name "~{VIA_CS}") (class "Default")
      (node (ref "IC16") (pin "23") (pinfunction "~{CS2B}_23") (pintype "input"))
      (node (ref "IC18") (pin "23") (pinfunction "~{CS2B}_23") (pintype "input"))
      (node (ref "IC9") (pin "12") (pinfunction "Y0_12") (pintype "output"))
      (node (ref "JP6") (pin "9") (pinfunction "9_9") (pintype "passive"))
    )
  )
)
